# ProPrj_JS203-39-FIBER-3_2024-11-07.net
KiCad netlist of a schematic drawn in EasyEDA Pro
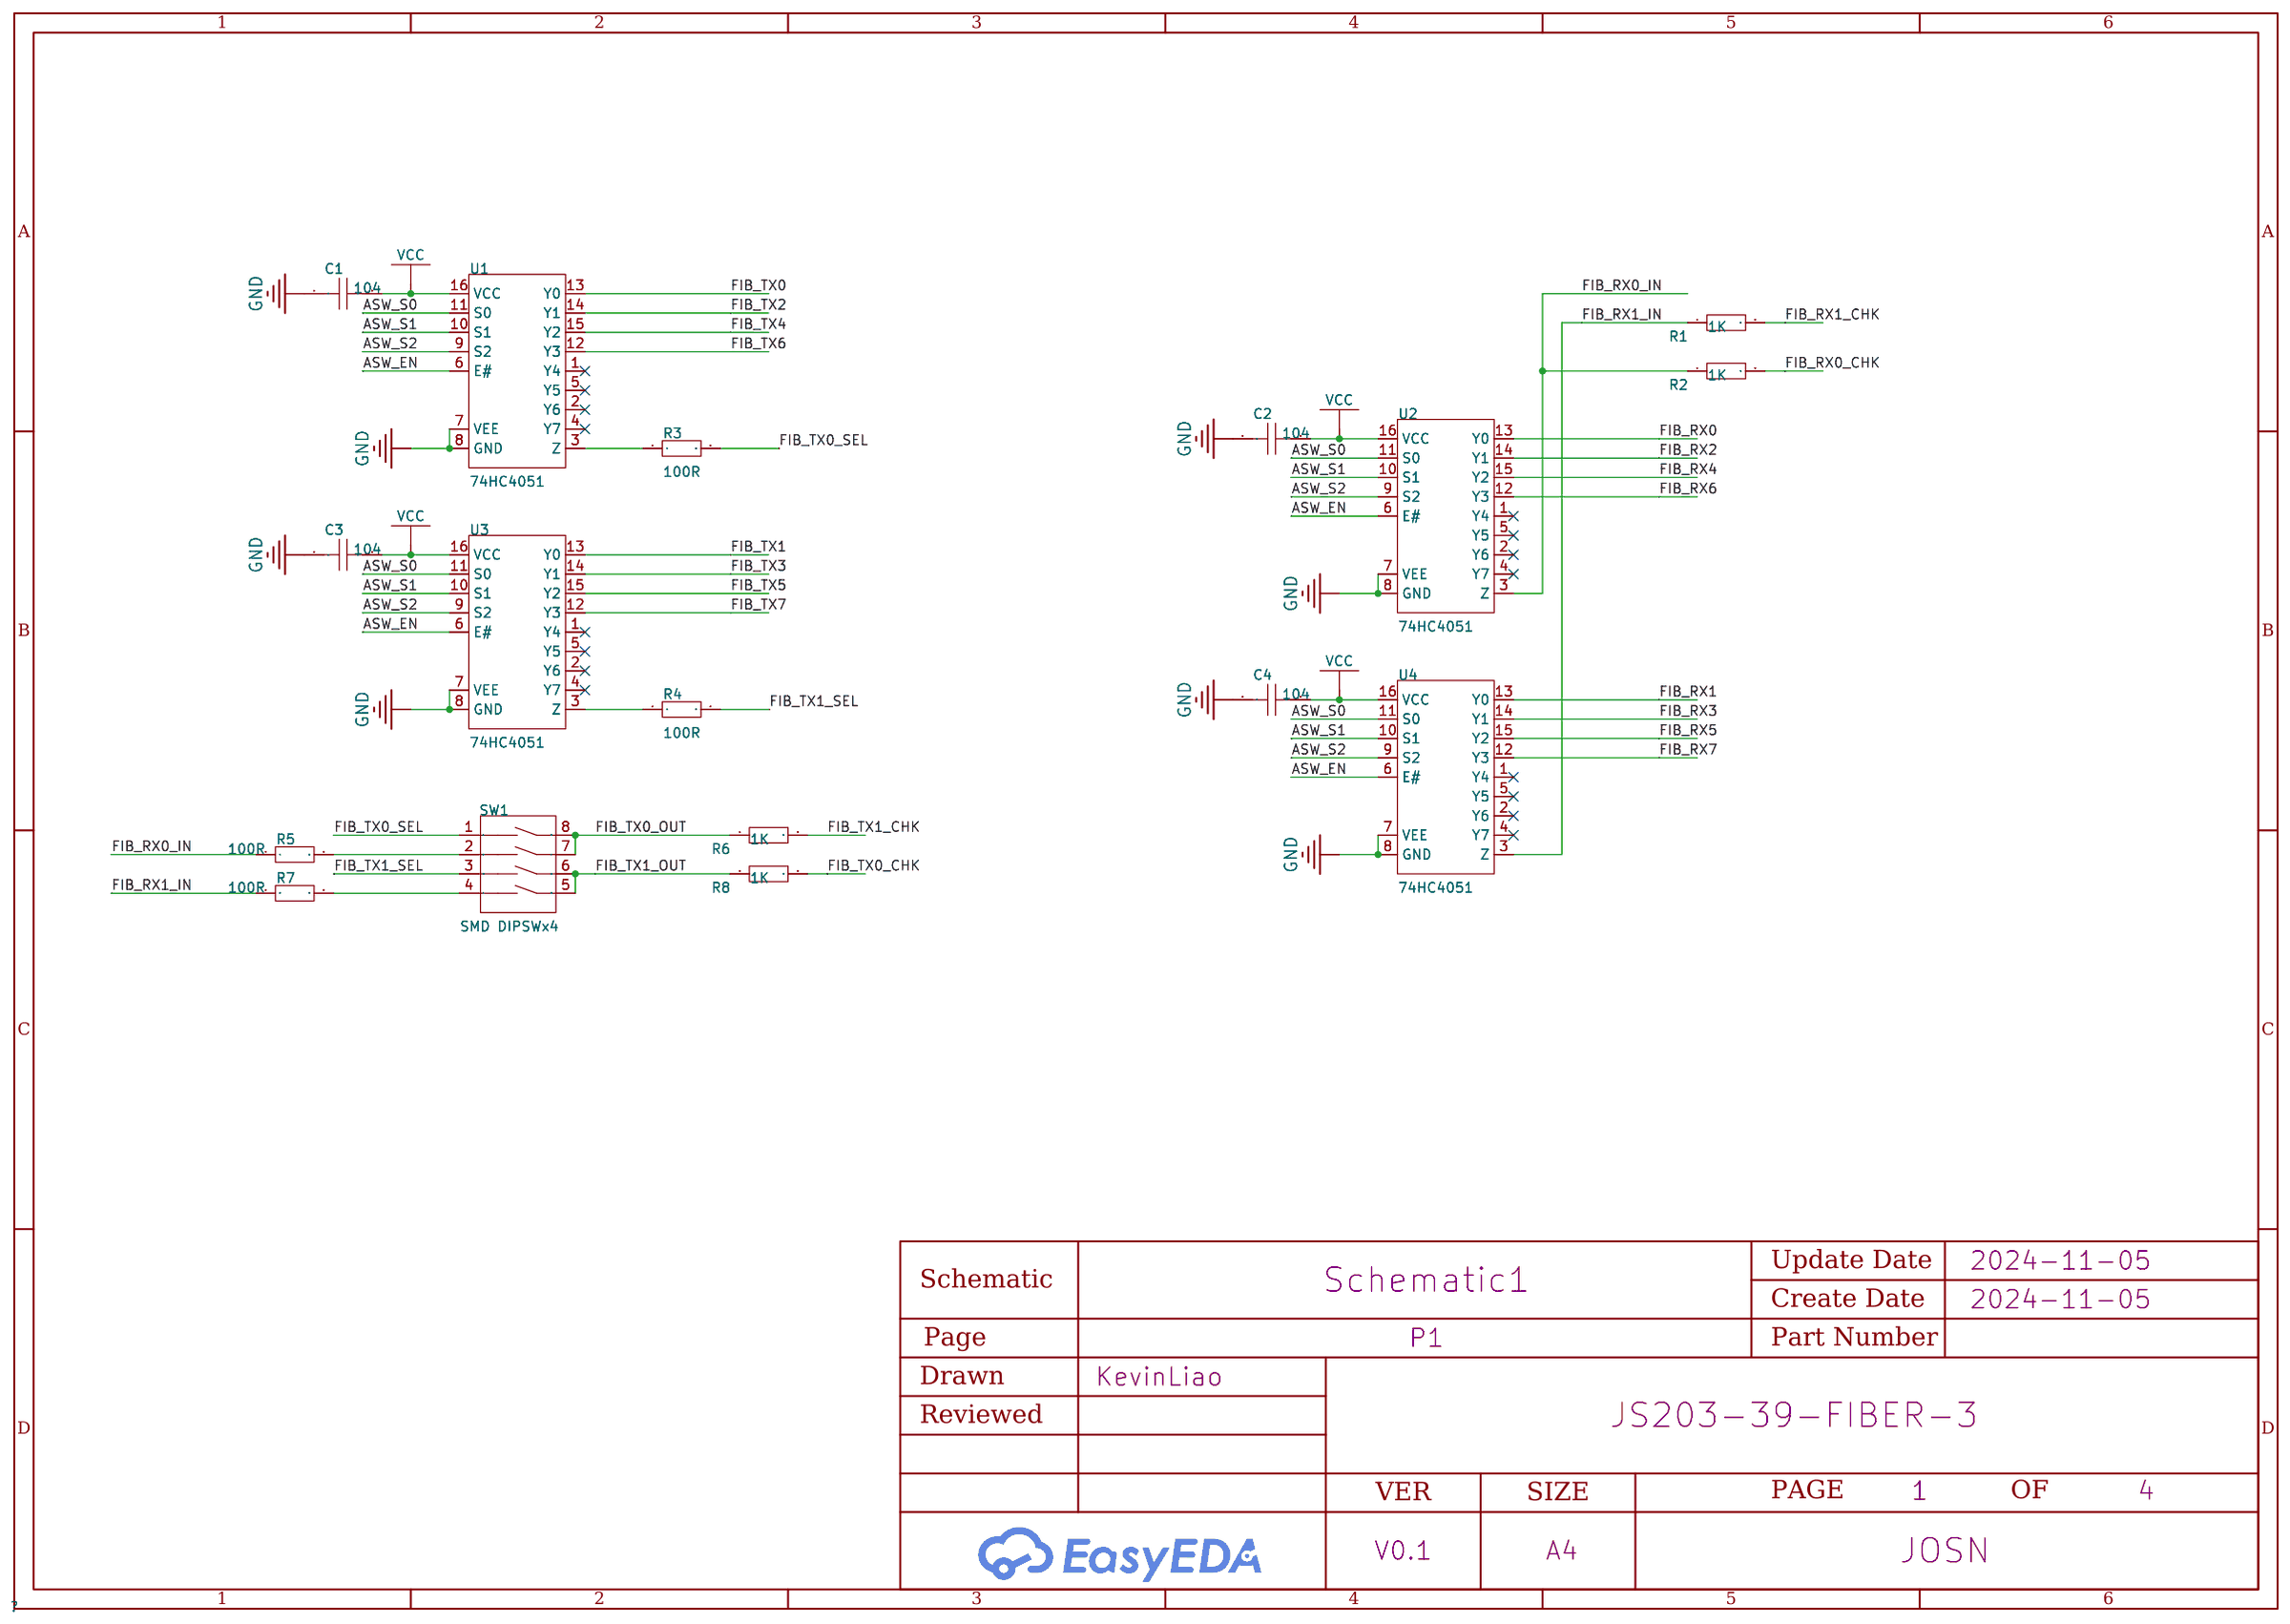
[diagram p0: P1]
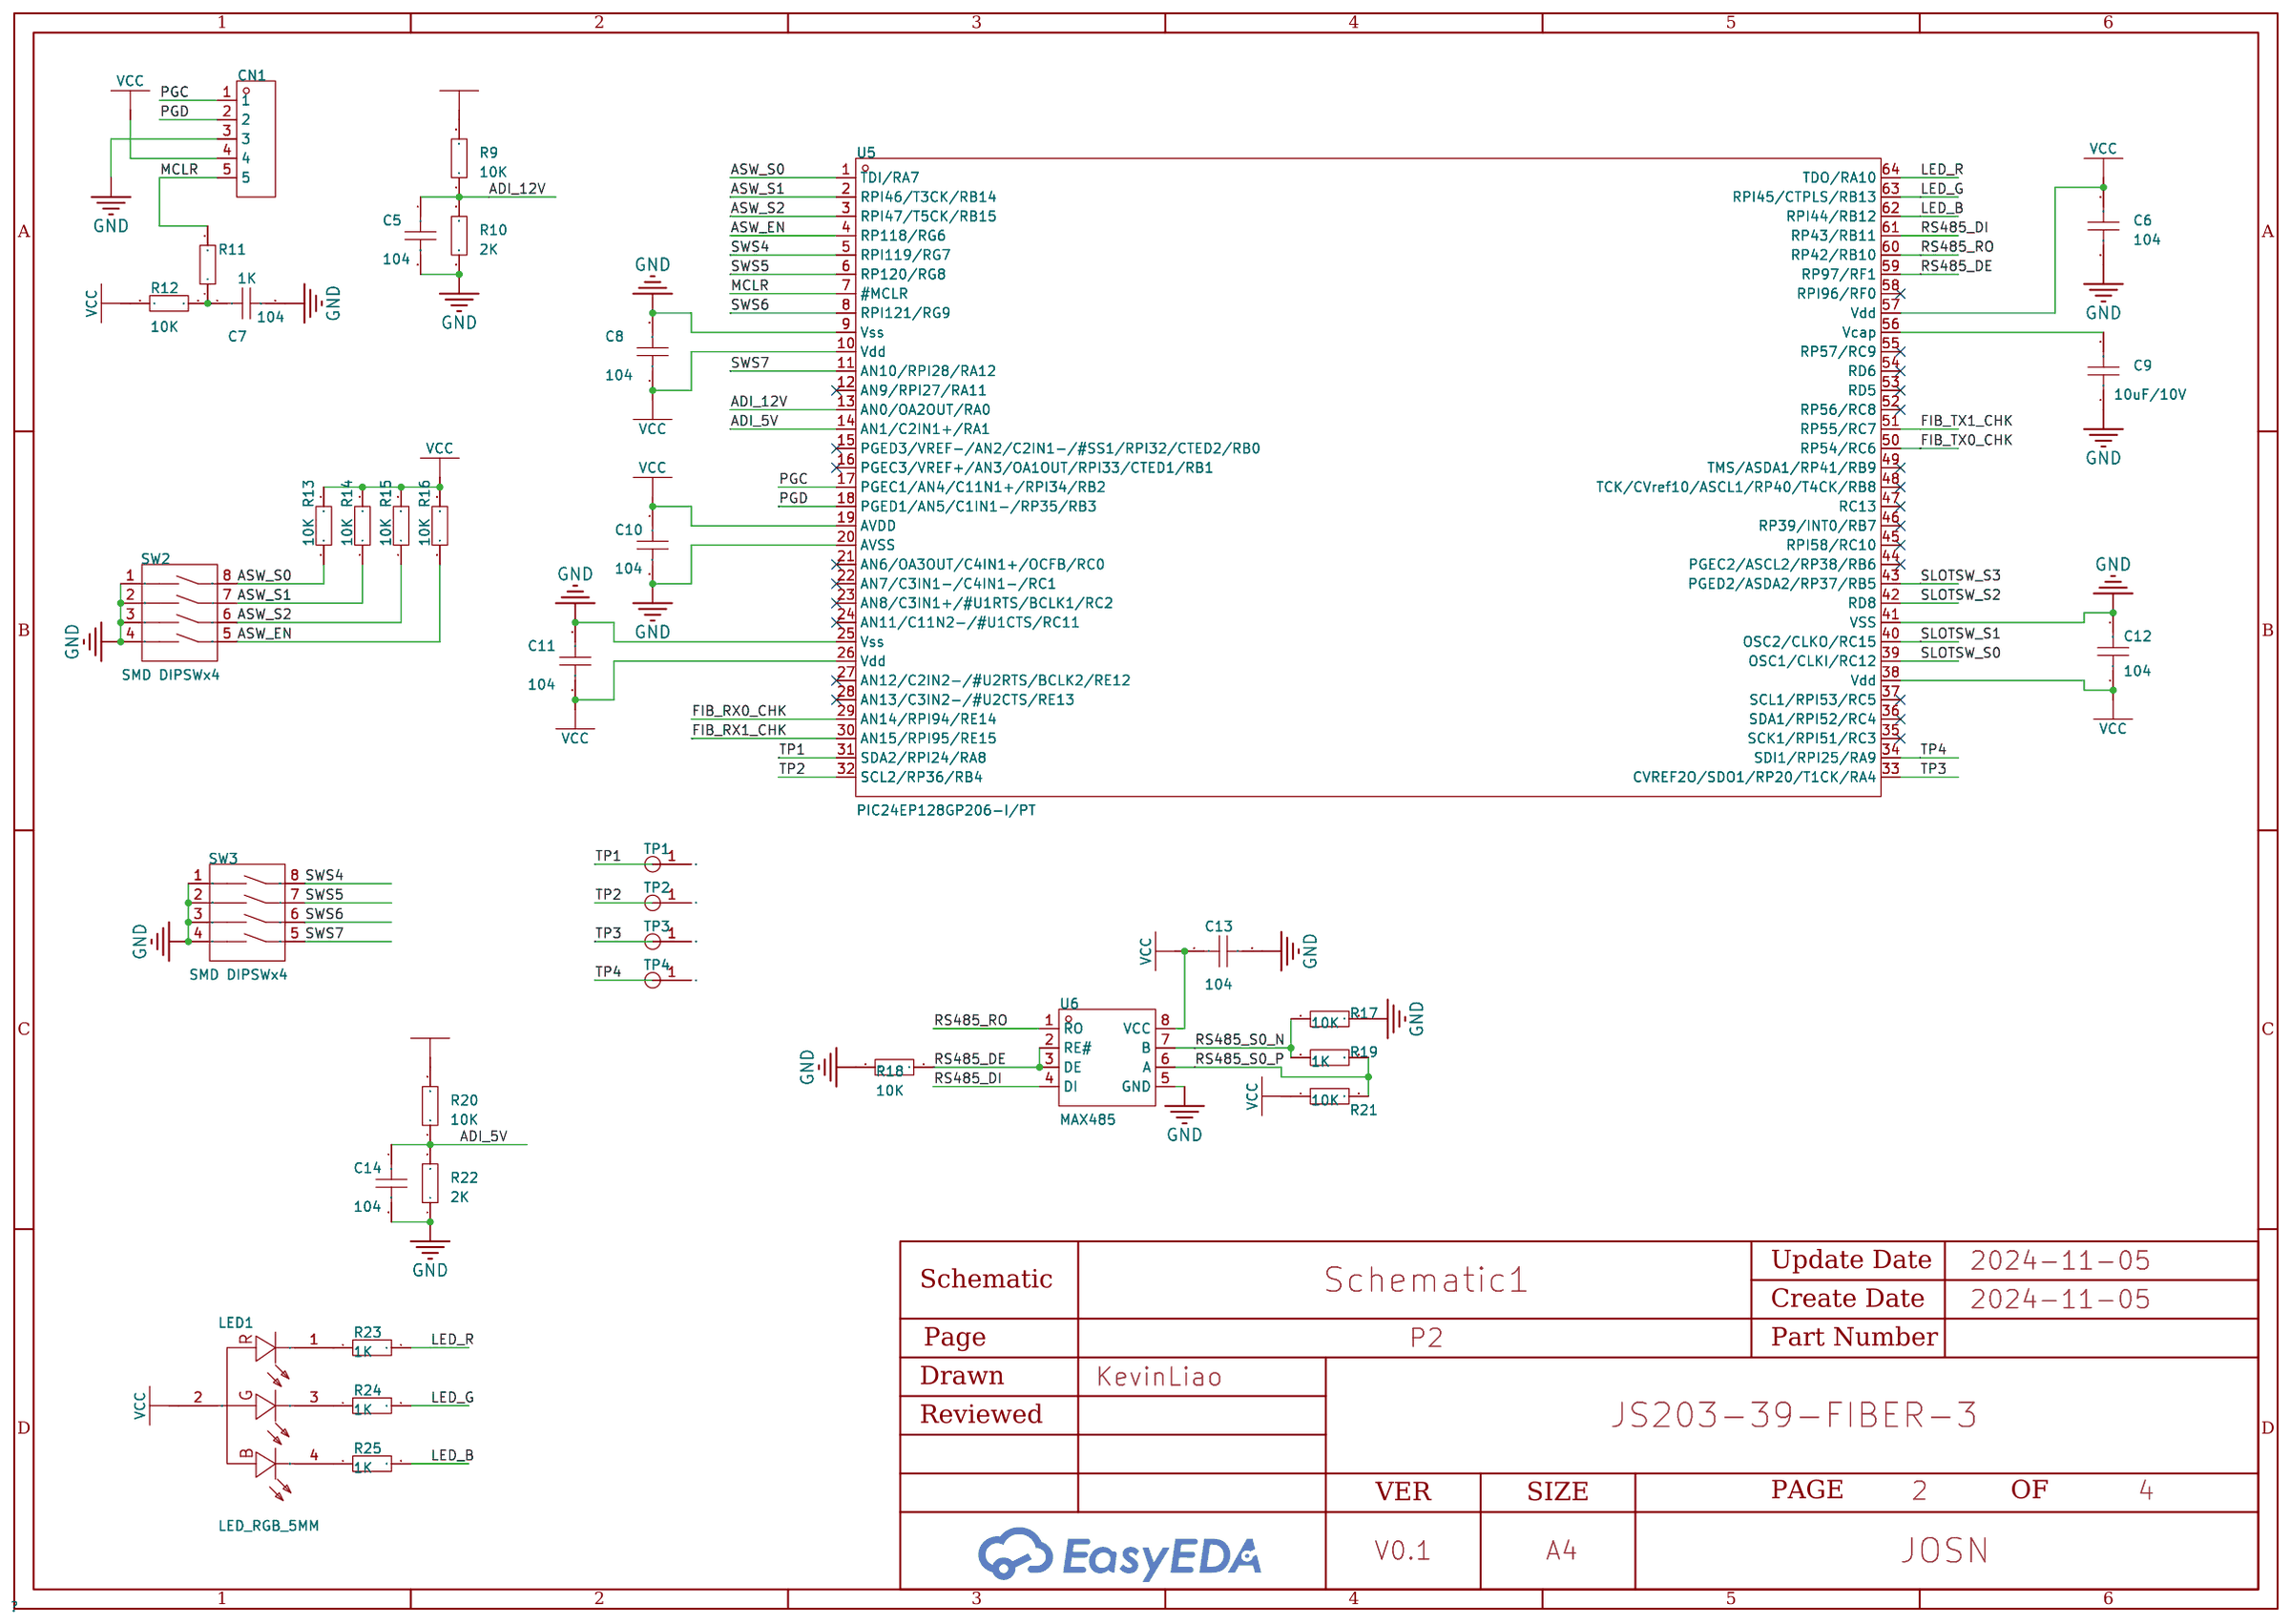
[diagram p1: P2]
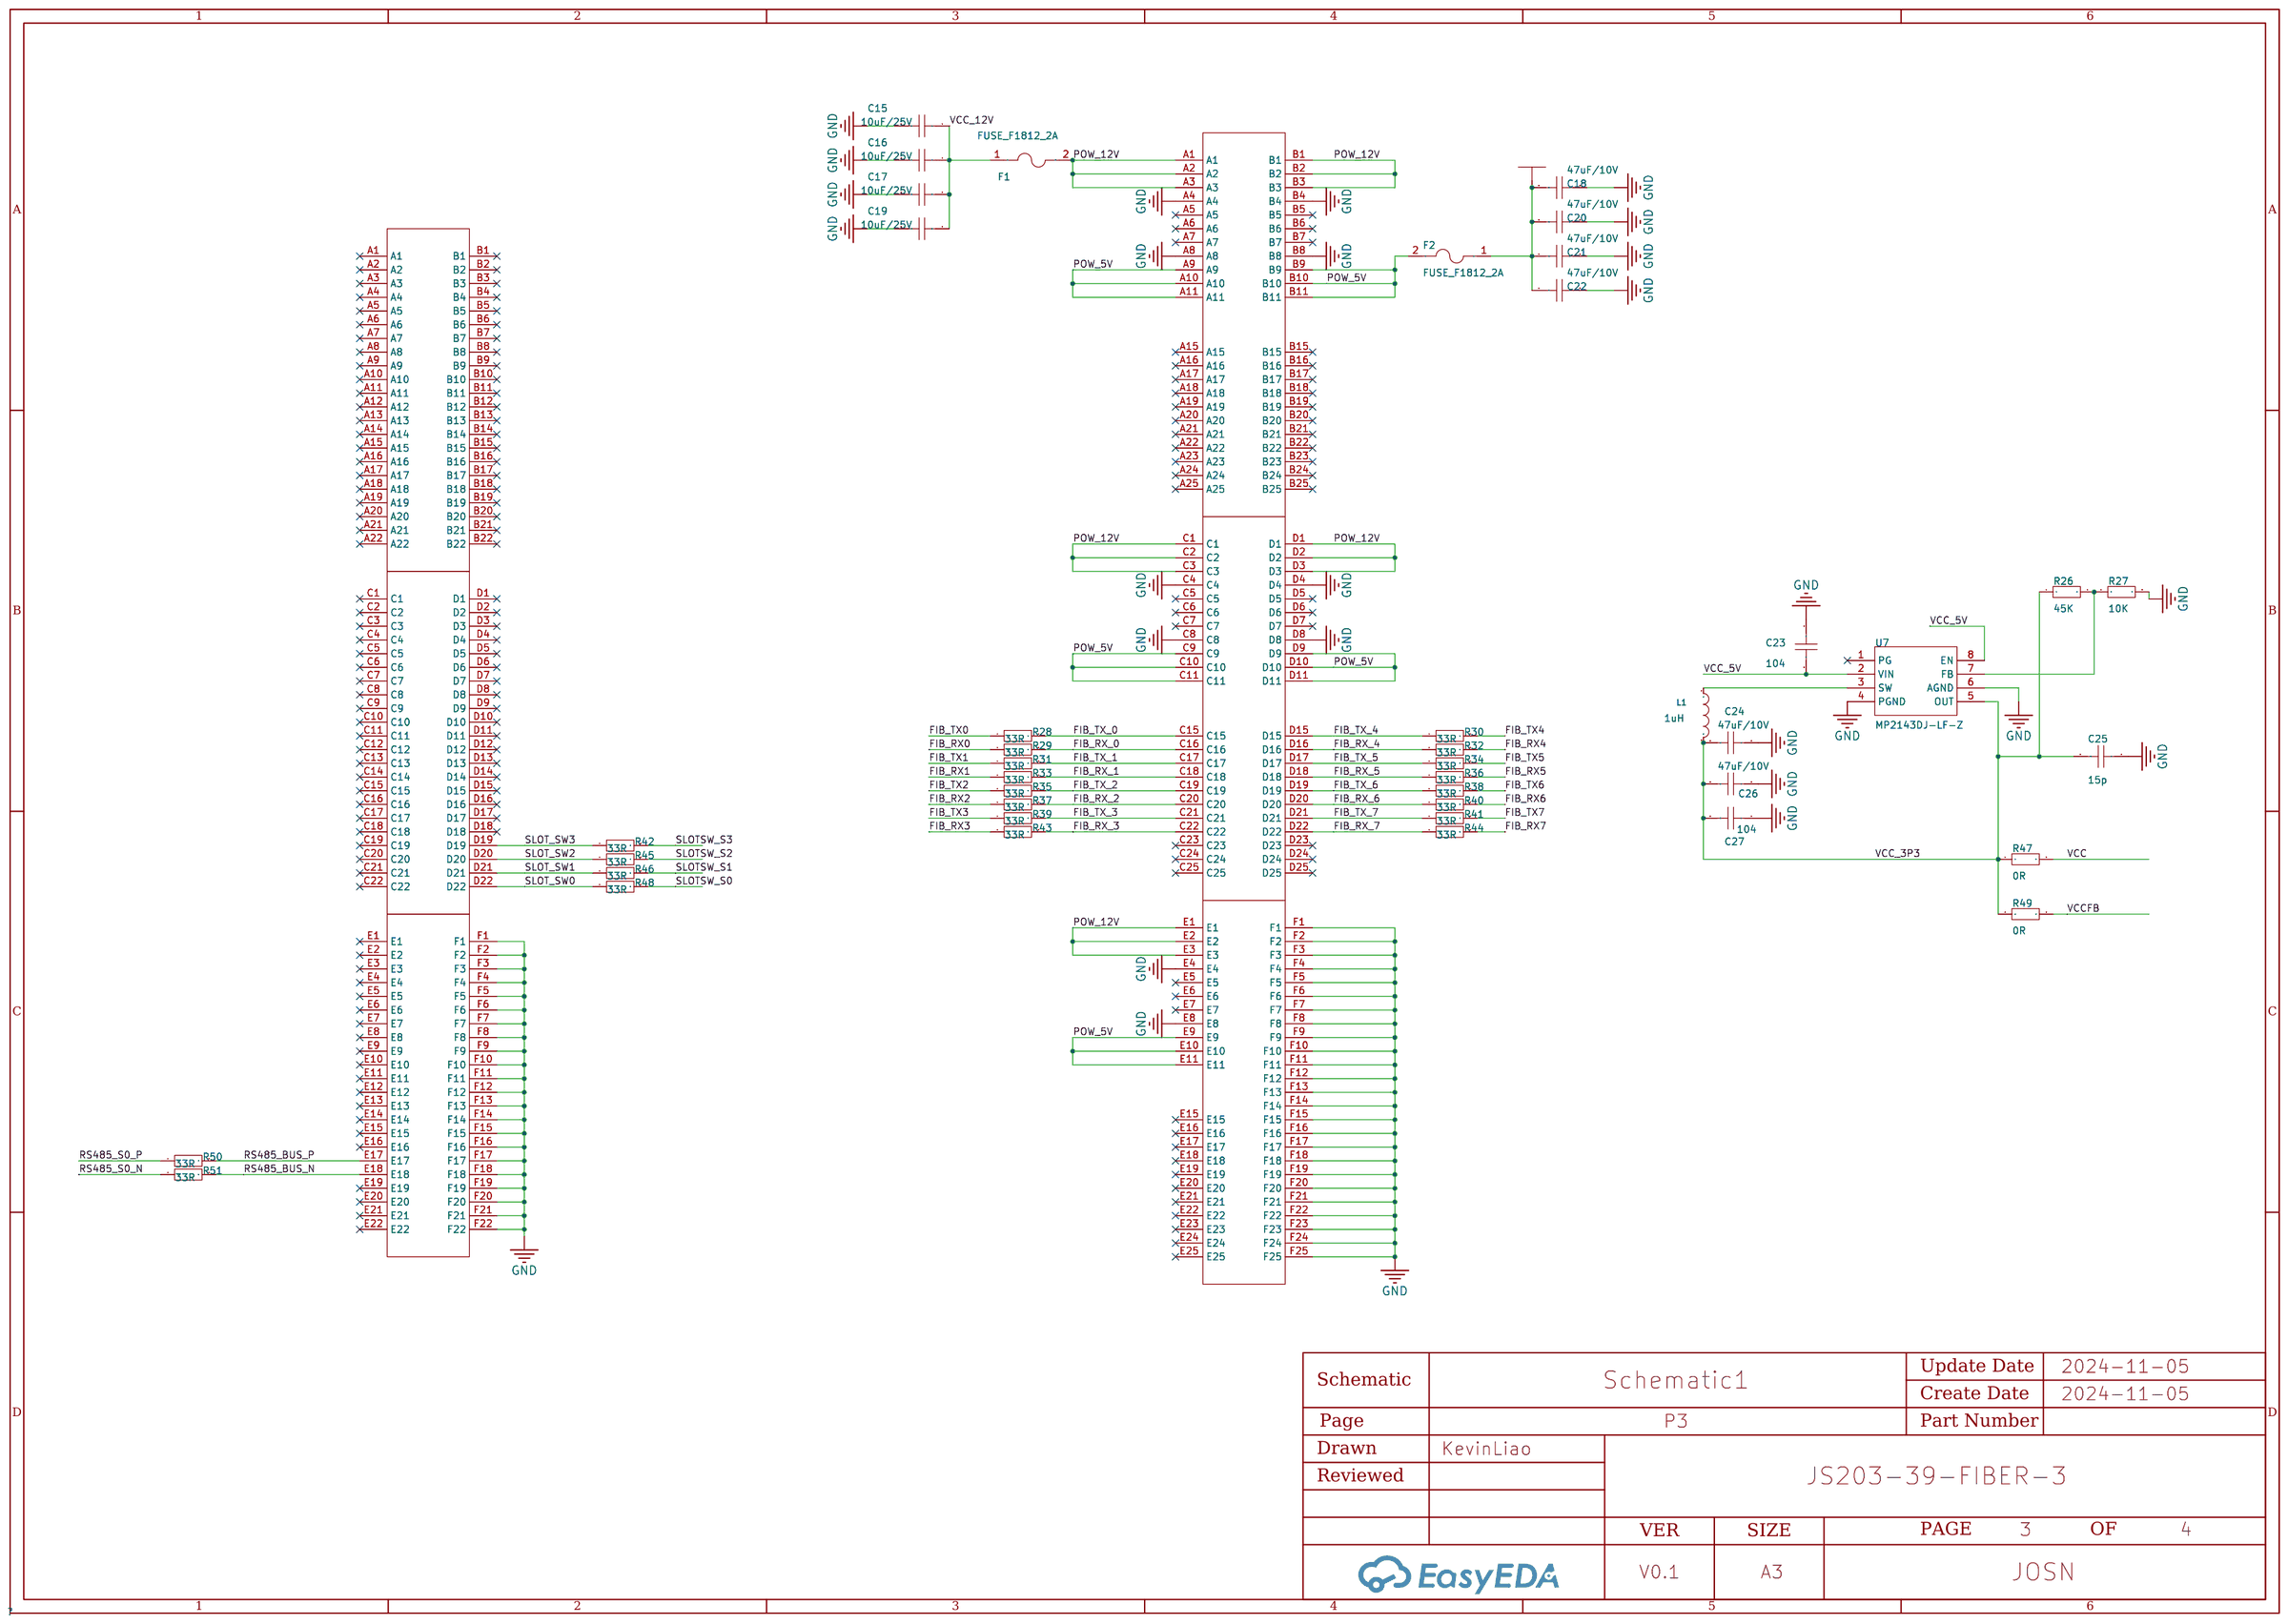
[diagram p2: P3]
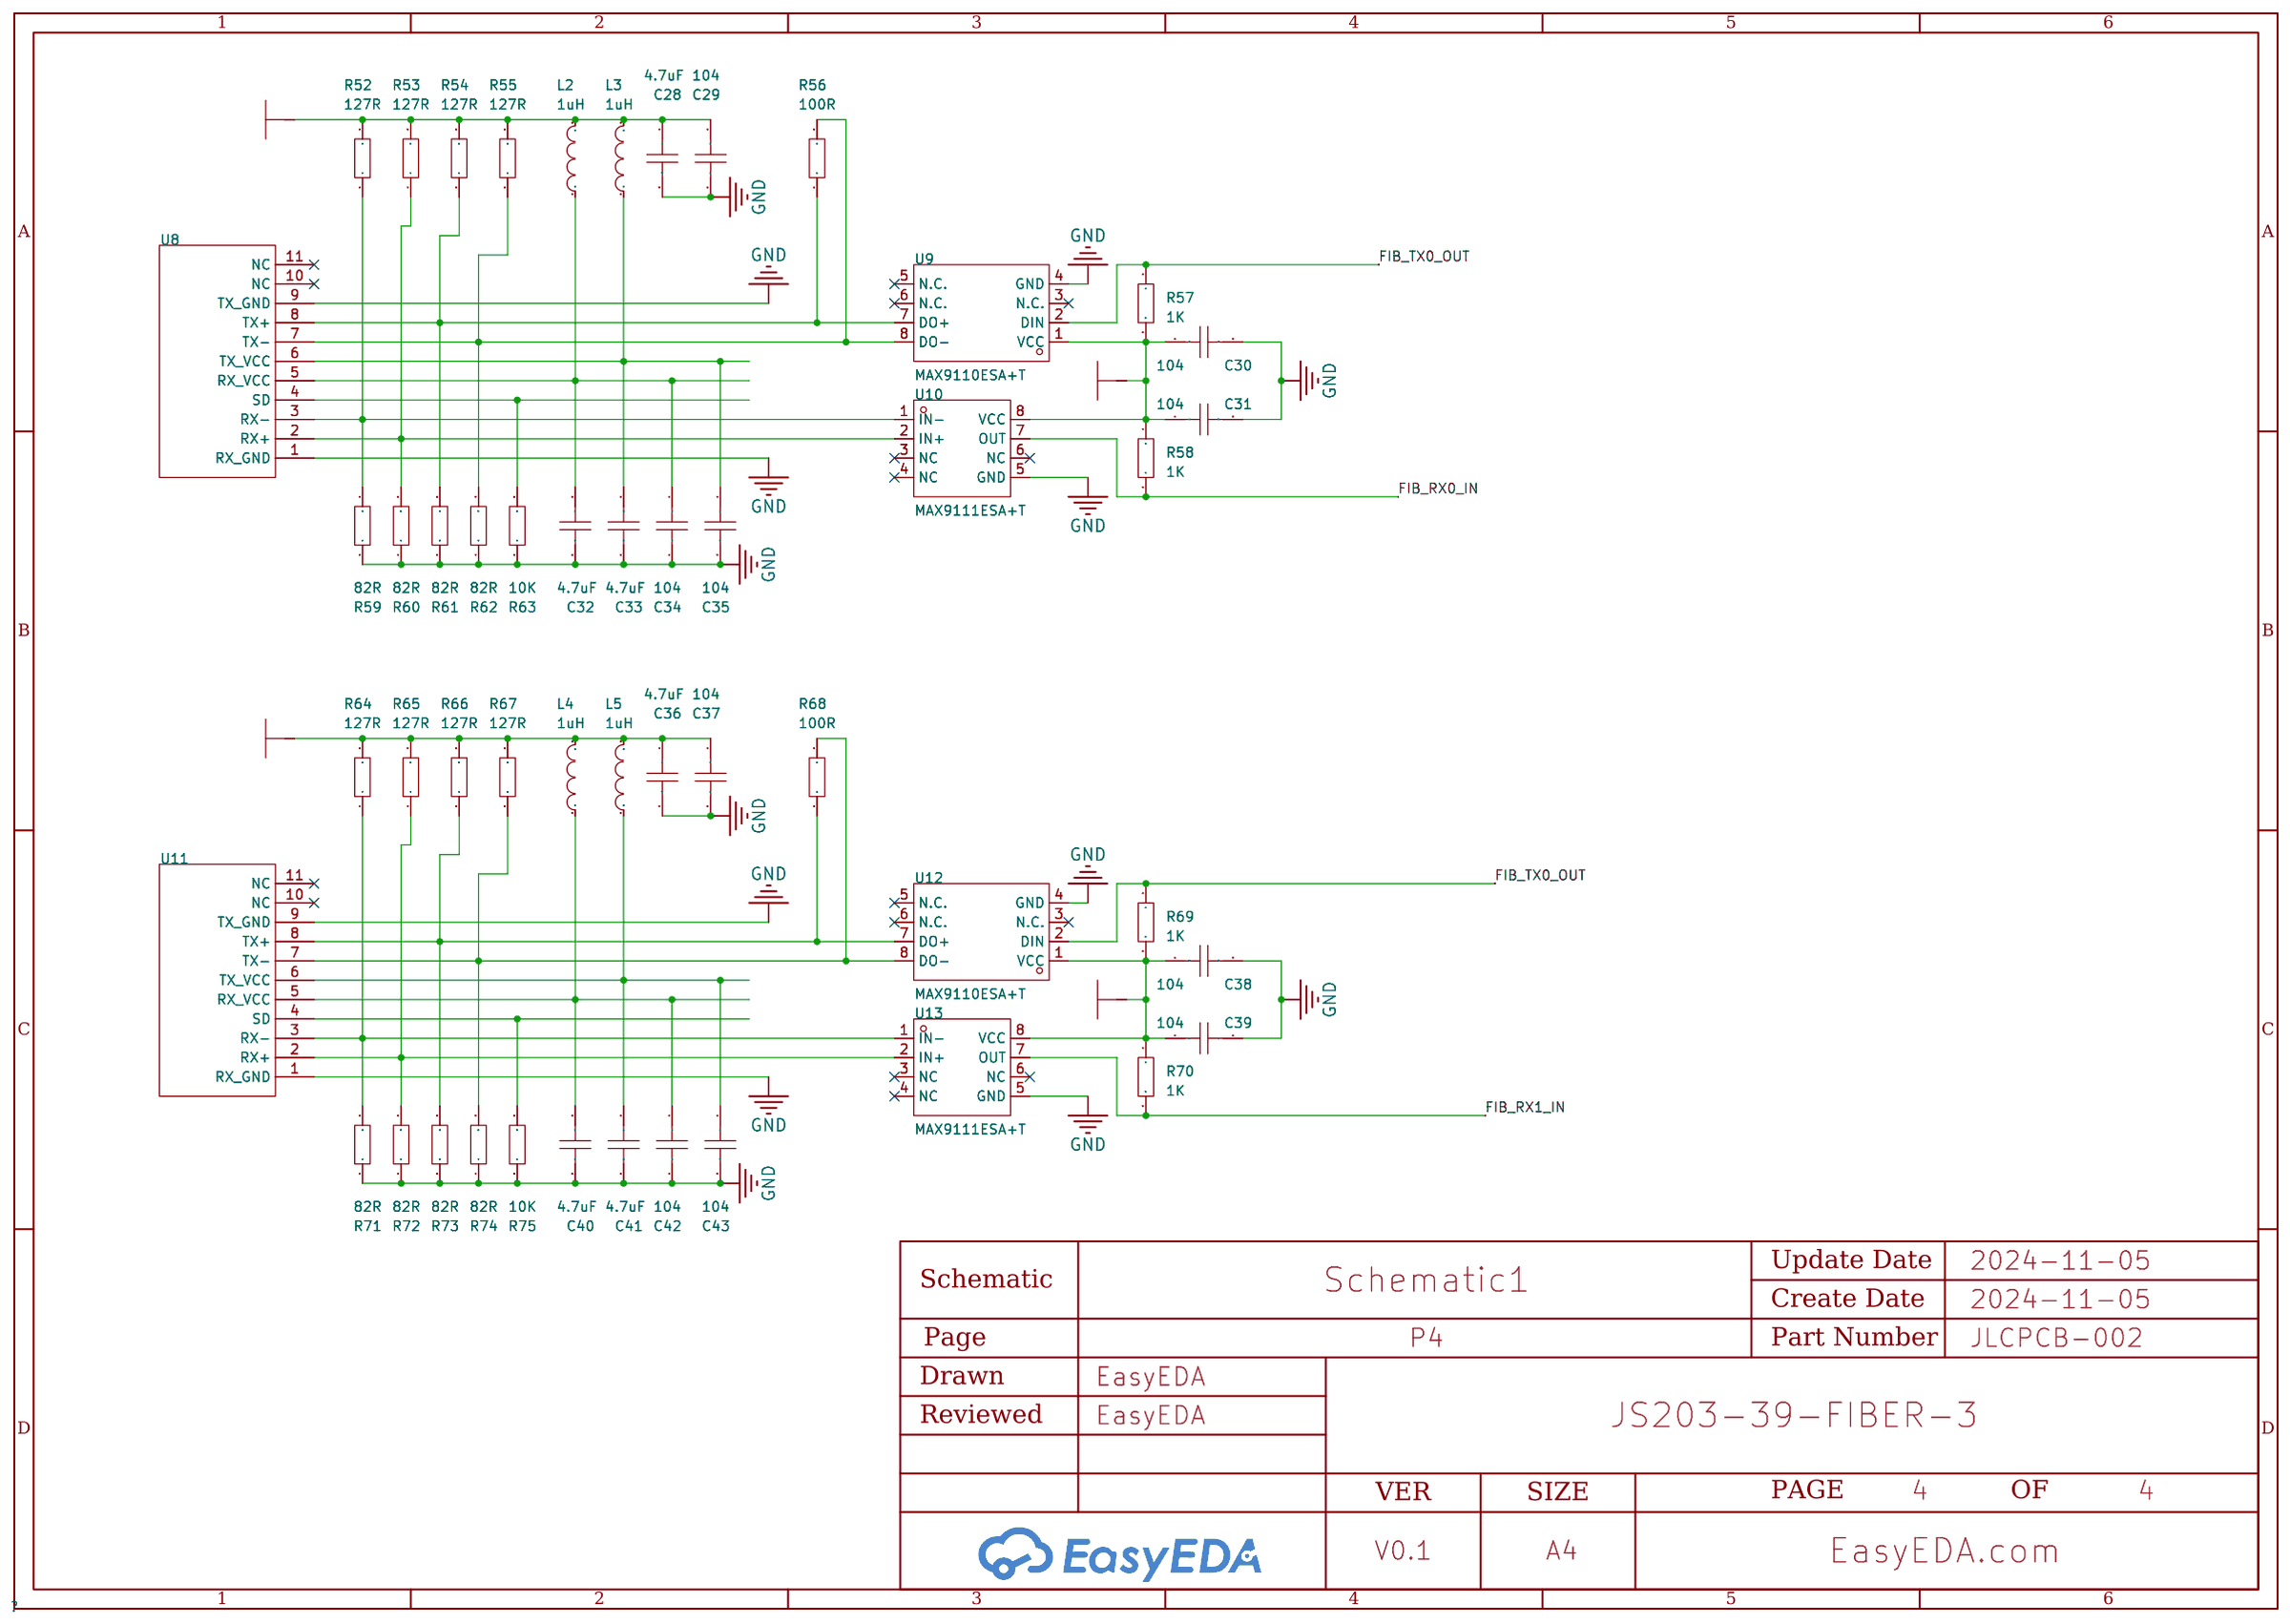
[diagram p3: P4]

(export (version "E")
  (design (tool "Eeschema 10.0.6"))
  (components
    (comp (ref "C1") (value "104") (footprint "easyedapro:C0603") (libsource (lib "easyedapro") (part "CAP")))
    (comp (ref "C2") (value "104") (footprint "easyedapro:C0603") (libsource (lib "easyedapro") (part "CAP")))
    (comp (ref "C3") (value "104") (footprint "easyedapro:C0603") (libsource (lib "easyedapro") (part "CAP")))
    (comp (ref "C4") (value "104") (footprint "easyedapro:C0603") (libsource (lib "easyedapro") (part "CAP")))
    (comp (ref "R1") (value "1K") (footprint "easyedapro:R0402") (libsource (lib "easyedapro") (part "Res")))
    (comp (ref "R2") (value "1K") (footprint "easyedapro:R0402") (libsource (lib "easyedapro") (part "Res")))
    (comp (ref "R3")
      (value "100R")
      (footprint "easyedapro:R0402")
      (libsource (lib "easyedapro") (part "Res"))
    )
    (comp (ref "R4")
      (value "100R")
      (footprint "easyedapro:R0402")
      (libsource (lib "easyedapro") (part "Res"))
    )
    (comp (ref "R5")
      (value "100R")
      (footprint "easyedapro:R0402")
      (libsource (lib "easyedapro") (part "Res"))
    )
    (comp (ref "R6") (value "1K") (footprint "easyedapro:R0402") (libsource (lib "easyedapro") (part "Res")))
    (comp (ref "R7")
      (value "100R")
      (footprint "easyedapro:R0402")
      (libsource (lib "easyedapro") (part "Res"))
    )
    (comp (ref "R8") (value "1K") (footprint "easyedapro:R0402") (libsource (lib "easyedapro") (part "Res")))
    (comp (ref "SW1")
      (value "SMD DIPSWx4")
      (footprint "easyedapro:SW-SMD_8P-L6.7-W5.4-P1.27-LS8.4")
      (libsource (lib "easyedapro") (part "DSHP04TSGER_C9900017355"))
    )
    (comp (ref "U1")
      (value "74HC4051")
      (footprint "easyedapro:TSSOP-16_L5.0-W4.4-P0.65-LS6.4-BL-1")
      (fields (field (name "Manufacturer") "onsemi(安森美)"))
      (libsource (lib "easyedapro") (part "MM74HC4051MTCX"))
    )
    (comp (ref "U2")
      (value "74HC4051")
      (footprint "easyedapro:TSSOP-16_L5.0-W4.4-P0.65-LS6.4-BL-1")
      (fields (field (name "Manufacturer") "onsemi(安森美)"))
      (libsource (lib "easyedapro") (part "MM74HC4051MTCX"))
    )
    (comp (ref "U3")
      (value "74HC4051")
      (footprint "easyedapro:TSSOP-16_L5.0-W4.4-P0.65-LS6.4-BL-1")
      (fields (field (name "Manufacturer") "onsemi(安森美)"))
      (libsource (lib "easyedapro") (part "MM74HC4051MTCX"))
    )
    (comp (ref "U4")
      (value "74HC4051")
      (footprint "easyedapro:TSSOP-16_L5.0-W4.4-P0.65-LS6.4-BL-1")
      (fields (field (name "Manufacturer") "onsemi(安森美)"))
      (libsource (lib "easyedapro") (part "MM74HC4051MTCX"))
    )
    (comp (ref "C5") (value "104") (footprint "easyedapro:C0603") (libsource (lib "easyedapro") (part "CAP")))
    (comp (ref "C6") (value "104") (footprint "easyedapro:C0603") (libsource (lib "easyedapro") (part "CAP")))
    (comp (ref "C7") (value "104") (footprint "easyedapro:C0603") (libsource (lib "easyedapro") (part "CAP")))
    (comp (ref "C8") (value "104") (footprint "easyedapro:C0603") (libsource (lib "easyedapro") (part "CAP")))
    (comp (ref "C9")
      (value "10uF/10V")
      (footprint "easyedapro:C0603")
      (libsource (lib "easyedapro") (part "CAP"))
    )
    (comp (ref "C10")
      (value "104")
      (footprint "easyedapro:C0603")
      (libsource (lib "easyedapro") (part "CAP"))
    )
    (comp (ref "C11")
      (value "104")
      (footprint "easyedapro:C0603")
      (libsource (lib "easyedapro") (part "CAP"))
    )
    (comp (ref "C12")
      (value "104")
      (footprint "easyedapro:C0603")
      (libsource (lib "easyedapro") (part "CAP"))
    )
    (comp (ref "C13")
      (value "104")
      (footprint "easyedapro:C0603")
      (libsource (lib "easyedapro") (part "CAP"))
    )
    (comp (ref "C14")
      (value "104")
      (footprint "easyedapro:C0603")
      (libsource (lib "easyedapro") (part "CAP"))
    )
    (comp (ref "CN1")
      (value "5PIN-2.0MM-90")
      (footprint "easyedapro:CONN-TH_5P-P2.00-PH5A")
      (libsource (lib "easyedapro") (part "5PIN-2.0MM-90"))
    )
    (comp (ref "LED1")
      (value "LED_RGB_5MM")
      (footprint "easyedapro:LED-TH_4P-BD5.8-P1.30")
      (libsource (lib "easyedapro") (part "三色灯2"))
    )
    (comp (ref "R9") (value "10K") (footprint "easyedapro:R0402") (libsource (lib "easyedapro") (part "Res")))
    (comp (ref "R10") (value "2K") (footprint "easyedapro:R0402") (libsource (lib "easyedapro") (part "Res")))
    (comp (ref "R11") (value "1K") (footprint "easyedapro:R0402") (libsource (lib "easyedapro") (part "Res")))
    (comp (ref "R12")
      (value "10K")
      (footprint "easyedapro:R0402")
      (libsource (lib "easyedapro") (part "Res"))
    )
    (comp (ref "R13")
      (value "10K")
      (footprint "easyedapro:R0402")
      (libsource (lib "easyedapro") (part "Res"))
    )
    (comp (ref "R14")
      (value "10K")
      (footprint "easyedapro:R0402")
      (libsource (lib "easyedapro") (part "Res"))
    )
    (comp (ref "R15")
      (value "10K")
      (footprint "easyedapro:R0402")
      (libsource (lib "easyedapro") (part "Res"))
    )
    (comp (ref "R16")
      (value "10K")
      (footprint "easyedapro:R0402")
      (libsource (lib "easyedapro") (part "Res"))
    )
    (comp (ref "R17")
      (value "10K")
      (footprint "easyedapro:R0402")
      (libsource (lib "easyedapro") (part "Res"))
    )
    (comp (ref "R18")
      (value "10K")
      (footprint "easyedapro:R0402")
      (libsource (lib "easyedapro") (part "Res"))
    )
    (comp (ref "R19") (value "1K") (footprint "easyedapro:R0402") (libsource (lib "easyedapro") (part "Res")))
    (comp (ref "R20")
      (value "10K")
      (footprint "easyedapro:R0402")
      (libsource (lib "easyedapro") (part "Res"))
    )
    (comp (ref "R21")
      (value "10K")
      (footprint "easyedapro:R0402")
      (libsource (lib "easyedapro") (part "Res"))
    )
    (comp (ref "R22") (value "2K") (footprint "easyedapro:R0402") (libsource (lib "easyedapro") (part "Res")))
    (comp (ref "R23") (value "1K") (footprint "easyedapro:R0402") (libsource (lib "easyedapro") (part "Res")))
    (comp (ref "R24") (value "1K") (footprint "easyedapro:R0402") (libsource (lib "easyedapro") (part "Res")))
    (comp (ref "R25") (value "1K") (footprint "easyedapro:R0402") (libsource (lib "easyedapro") (part "Res")))
    (comp (ref "SW2")
      (value "SMD DIPSWx4")
      (footprint "easyedapro:SW-SMD_8P-L6.7-W5.4-P1.27-LS8.4")
      (libsource (lib "easyedapro") (part "DSHP04TSGER_C9900017355"))
    )
    (comp (ref "SW3")
      (value "SMD DIPSWx4")
      (footprint "easyedapro:SW-SMD_8P-L6.7-W5.4-P1.27-LS8.4")
      (libsource (lib "easyedapro") (part "DSHP04TSGER_C9900017355"))
    )
    (comp (ref "TP1")
      (value "~")
      (footprint "easyedapro:testPoint")
      (libsource (lib "easyedapro") (part "testPoint"))
    )
    (comp (ref "TP2")
      (value "~")
      (footprint "easyedapro:testPoint")
      (libsource (lib "easyedapro") (part "testPoint"))
    )
    (comp (ref "TP3")
      (value "~")
      (footprint "easyedapro:testPoint")
      (libsource (lib "easyedapro") (part "testPoint"))
    )
    (comp (ref "TP4")
      (value "~")
      (footprint "easyedapro:testPoint")
      (libsource (lib "easyedapro") (part "testPoint"))
    )
    (comp (ref "U5")
      (value "PIC24EP128GP206-I/PT")
      (footprint "easyedapro:TQFP-64_L10.0-W10.0-P0.50-LS12.0-BL")
      (fields (field (name "Manufacturer") "MICROCHIP(美国微芯)"))
      (libsource (lib "easyedapro") (part "PIC24EP128GP206-I/PT"))
    )
    (comp (ref "U6")
      (value "MAX485")
      (footprint "easyedapro:SOIC-8_L5.0-W4.0-P1.27-LS6.0-BL")
      (fields (field (name "Manufacturer") "MSKSEMI(美森科)"))
      (libsource (lib "easyedapro") (part "MAX485ESA-MS"))
    )
    (comp (ref "C15")
      (value "10uF/25V")
      (footprint "easyedapro:C0603")
      (libsource (lib "easyedapro") (part "CAP"))
    )
    (comp (ref "C16")
      (value "10uF/25V")
      (footprint "easyedapro:C0603")
      (libsource (lib "easyedapro") (part "CAP"))
    )
    (comp (ref "C17")
      (value "10uF/25V")
      (footprint "easyedapro:C0603")
      (libsource (lib "easyedapro") (part "CAP"))
    )
    (comp (ref "C18")
      (value "47uF/10V")
      (footprint "easyedapro:C0603")
      (libsource (lib "easyedapro") (part "CAP"))
    )
    (comp (ref "C19")
      (value "10uF/25V")
      (footprint "easyedapro:C0603")
      (libsource (lib "easyedapro") (part "CAP"))
    )
    (comp (ref "C20")
      (value "47uF/10V")
      (footprint "easyedapro:C0603")
      (libsource (lib "easyedapro") (part "CAP"))
    )
    (comp (ref "C21")
      (value "47uF/10V")
      (footprint "easyedapro:C0603")
      (libsource (lib "easyedapro") (part "CAP"))
    )
    (comp (ref "C22")
      (value "47uF/10V")
      (footprint "easyedapro:C0603")
      (libsource (lib "easyedapro") (part "CAP"))
    )
    (comp (ref "C23")
      (value "104")
      (footprint "easyedapro:C0603")
      (libsource (lib "easyedapro") (part "CAP"))
    )
    (comp (ref "C24")
      (value "47uF/10V")
      (footprint "easyedapro:C0603")
      (libsource (lib "easyedapro") (part "CAP"))
    )
    (comp (ref "C25")
      (value "15p")
      (footprint "easyedapro:C0603")
      (libsource (lib "easyedapro") (part "CAP"))
    )
    (comp (ref "C26")
      (value "47uF/10V")
      (footprint "easyedapro:C0603")
      (libsource (lib "easyedapro") (part "CAP"))
    )
    (comp (ref "C27")
      (value "104")
      (footprint "easyedapro:C0603")
      (libsource (lib "easyedapro") (part "CAP"))
    )
    (comp (ref "CON1") (value "CPCI-CON-B") (libsource (lib "easyedapro") (part "pci-con-b")))
    (comp (ref "CON2") (value "CPCI-CON-A") (libsource (lib "easyedapro") (part "cpci-con-a")))
    (comp (ref "F1")
      (value "FUSE_F1812_2A")
      (footprint "easyedapro:F1812")
      (libsource (lib "easyedapro") (part "FUSE_F1812_FUSE"))
    )
    (comp (ref "F2")
      (value "FUSE_F1812_2A")
      (footprint "easyedapro:F1812")
      (libsource (lib "easyedapro") (part "FUSE_F1812_FUSE"))
    )
    (comp (ref "L1")
      (value "1uH")
      (footprint "easyedapro:IND-SMD_L4.0-W4.0-A")
      (fields
        (field (name "Manufacturer Part") "XFL4020-152MEC")
        (field (name "Manufacturer") "Coilcraft(线艺)")
      )
      (libsource (lib "easyedapro") (part "XFL4020-152MEC"))
    )
    (comp (ref "R26")
      (value "45K")
      (footprint "easyedapro:R0402")
      (libsource (lib "easyedapro") (part "Res"))
    )
    (comp (ref "R27")
      (value "10K")
      (footprint "easyedapro:R0402")
      (libsource (lib "easyedapro") (part "Res"))
    )
    (comp (ref "R28")
      (value "33R")
      (footprint "easyedapro:R0402")
      (libsource (lib "easyedapro") (part "Res"))
    )
    (comp (ref "R29")
      (value "33R")
      (footprint "easyedapro:R0402")
      (libsource (lib "easyedapro") (part "Res"))
    )
    (comp (ref "R30")
      (value "33R")
      (footprint "easyedapro:R0402")
      (libsource (lib "easyedapro") (part "Res"))
    )
    (comp (ref "R31")
      (value "33R")
      (footprint "easyedapro:R0402")
      (libsource (lib "easyedapro") (part "Res"))
    )
    (comp (ref "R32")
      (value "33R")
      (footprint "easyedapro:R0402")
      (libsource (lib "easyedapro") (part "Res"))
    )
    (comp (ref "R33")
      (value "33R")
      (footprint "easyedapro:R0402")
      (libsource (lib "easyedapro") (part "Res"))
    )
    (comp (ref "R34")
      (value "33R")
      (footprint "easyedapro:R0402")
      (libsource (lib "easyedapro") (part "Res"))
    )
    (comp (ref "R35")
      (value "33R")
      (footprint "easyedapro:R0402")
      (libsource (lib "easyedapro") (part "Res"))
    )
    (comp (ref "R36")
      (value "33R")
      (footprint "easyedapro:R0402")
      (libsource (lib "easyedapro") (part "Res"))
    )
    (comp (ref "R37")
      (value "33R")
      (footprint "easyedapro:R0402")
      (libsource (lib "easyedapro") (part "Res"))
    )
    (comp (ref "R38")
      (value "33R")
      (footprint "easyedapro:R0402")
      (libsource (lib "easyedapro") (part "Res"))
    )
    (comp (ref "R39")
      (value "33R")
      (footprint "easyedapro:R0402")
      (libsource (lib "easyedapro") (part "Res"))
    )
    (comp (ref "R40")
      (value "33R")
      (footprint "easyedapro:R0402")
      (libsource (lib "easyedapro") (part "Res"))
    )
    (comp (ref "R41")
      (value "33R")
      (footprint "easyedapro:R0402")
      (libsource (lib "easyedapro") (part "Res"))
    )
    (comp (ref "R42")
      (value "33R")
      (footprint "easyedapro:R0402")
      (libsource (lib "easyedapro") (part "Res"))
    )
    (comp (ref "R43")
      (value "33R")
      (footprint "easyedapro:R0402")
      (libsource (lib "easyedapro") (part "Res"))
    )
    (comp (ref "R44")
      (value "33R")
      (footprint "easyedapro:R0402")
      (libsource (lib "easyedapro") (part "Res"))
    )
    (comp (ref "R45")
      (value "33R")
      (footprint "easyedapro:R0402")
      (libsource (lib "easyedapro") (part "Res"))
    )
    (comp (ref "R46")
      (value "33R")
      (footprint "easyedapro:R0402")
      (libsource (lib "easyedapro") (part "Res"))
    )
    (comp (ref "R47") (value "0R") (footprint "easyedapro:R0402") (libsource (lib "easyedapro") (part "Res")))
    (comp (ref "R48")
      (value "33R")
      (footprint "easyedapro:R0402")
      (libsource (lib "easyedapro") (part "Res"))
    )
    (comp (ref "R49") (value "0R") (footprint "easyedapro:R0402") (libsource (lib "easyedapro") (part "Res")))
    (comp (ref "R50")
      (value "33R")
      (footprint "easyedapro:R0402")
      (libsource (lib "easyedapro") (part "Res"))
    )
    (comp (ref "R51")
      (value "33R")
      (footprint "easyedapro:R0402")
      (libsource (lib "easyedapro") (part "Res"))
    )
    (comp (ref "U7")
      (value "MP2143DJ-LF-Z")
      (footprint "easyedapro:TSOT-23-8_L2.9-W1.6-P0.65-LS2.8-BR")
      (libsource (lib "easyedapro") (part "MP2143DJ-LF-Z"))
    )
    (comp (ref "C28")
      (value "4.7uF")
      (footprint "easyedapro:C0603")
      (libsource (lib "easyedapro") (part "CAP"))
    )
    (comp (ref "C29")
      (value "104")
      (footprint "easyedapro:C0603")
      (libsource (lib "easyedapro") (part "CAP"))
    )
    (comp (ref "C30")
      (value "104")
      (footprint "easyedapro:C0603")
      (libsource (lib "easyedapro") (part "CAP"))
    )
    (comp (ref "C31")
      (value "104")
      (footprint "easyedapro:C0603")
      (libsource (lib "easyedapro") (part "CAP"))
    )
    (comp (ref "C32")
      (value "4.7uF")
      (footprint "easyedapro:C0603")
      (libsource (lib "easyedapro") (part "CAP"))
    )
    (comp (ref "C33")
      (value "4.7uF")
      (footprint "easyedapro:C0603")
      (libsource (lib "easyedapro") (part "CAP"))
    )
    (comp (ref "C34")
      (value "104")
      (footprint "easyedapro:C0603")
      (libsource (lib "easyedapro") (part "CAP"))
    )
    (comp (ref "C35")
      (value "104")
      (footprint "easyedapro:C0603")
      (libsource (lib "easyedapro") (part "CAP"))
    )
    (comp (ref "C36")
      (value "4.7uF")
      (footprint "easyedapro:C0603")
      (libsource (lib "easyedapro") (part "CAP"))
    )
    (comp (ref "C37")
      (value "104")
      (footprint "easyedapro:C0603")
      (libsource (lib "easyedapro") (part "CAP"))
    )
    (comp (ref "C38")
      (value "104")
      (footprint "easyedapro:C0603")
      (libsource (lib "easyedapro") (part "CAP"))
    )
    (comp (ref "C39")
      (value "104")
      (footprint "easyedapro:C0603")
      (libsource (lib "easyedapro") (part "CAP"))
    )
    (comp (ref "C40")
      (value "4.7uF")
      (footprint "easyedapro:C0603")
      (libsource (lib "easyedapro") (part "CAP"))
    )
    (comp (ref "C41")
      (value "4.7uF")
      (footprint "easyedapro:C0603")
      (libsource (lib "easyedapro") (part "CAP"))
    )
    (comp (ref "C42")
      (value "104")
      (footprint "easyedapro:C0603")
      (libsource (lib "easyedapro") (part "CAP"))
    )
    (comp (ref "C43")
      (value "104")
      (footprint "easyedapro:C0603")
      (libsource (lib "easyedapro") (part "CAP"))
    )
    (comp (ref "L2") (value "1uH") (footprint "easyedapro:L0805") (libsource (lib "easyedapro") (part "电感")))
    (comp (ref "L3") (value "1uH") (footprint "easyedapro:L0805") (libsource (lib "easyedapro") (part "电感")))
    (comp (ref "L4") (value "1uH") (footprint "easyedapro:L0805") (libsource (lib "easyedapro") (part "电感")))
    (comp (ref "L5") (value "1uH") (footprint "easyedapro:L0805") (libsource (lib "easyedapro") (part "电感")))
    (comp (ref "R52")
      (value "127R")
      (footprint "easyedapro:R0402")
      (libsource (lib "easyedapro") (part "Res"))
    )
    (comp (ref "R53")
      (value "127R")
      (footprint "easyedapro:R0402")
      (libsource (lib "easyedapro") (part "Res"))
    )
    (comp (ref "R54")
      (value "127R")
      (footprint "easyedapro:R0402")
      (libsource (lib "easyedapro") (part "Res"))
    )
    (comp (ref "R55")
      (value "127R")
      (footprint "easyedapro:R0402")
      (libsource (lib "easyedapro") (part "Res"))
    )
    (comp (ref "R56")
      (value "100R")
      (footprint "easyedapro:R0402")
      (libsource (lib "easyedapro") (part "Res"))
    )
    (comp (ref "R57") (value "1K") (footprint "easyedapro:R0402") (libsource (lib "easyedapro") (part "Res")))
    (comp (ref "R58") (value "1K") (footprint "easyedapro:R0402") (libsource (lib "easyedapro") (part "Res")))
    (comp (ref "R59")
      (value "82R")
      (footprint "easyedapro:R0402")
      (libsource (lib "easyedapro") (part "Res"))
    )
    (comp (ref "R60")
      (value "82R")
      (footprint "easyedapro:R0402")
      (libsource (lib "easyedapro") (part "Res"))
    )
    (comp (ref "R61")
      (value "82R")
      (footprint "easyedapro:R0402")
      (libsource (lib "easyedapro") (part "Res"))
    )
    (comp (ref "R62")
      (value "82R")
      (footprint "easyedapro:R0402")
      (libsource (lib "easyedapro") (part "Res"))
    )
    (comp (ref "R63")
      (value "10K")
      (footprint "easyedapro:R0402")
      (libsource (lib "easyedapro") (part "Res"))
    )
    (comp (ref "R64")
      (value "127R")
      (footprint "easyedapro:R0402")
      (libsource (lib "easyedapro") (part "Res"))
    )
    (comp (ref "R65")
      (value "127R")
      (footprint "easyedapro:R0402")
      (libsource (lib "easyedapro") (part "Res"))
    )
    (comp (ref "R66")
      (value "127R")
      (footprint "easyedapro:R0402")
      (libsource (lib "easyedapro") (part "Res"))
    )
    (comp (ref "R67")
      (value "127R")
      (footprint "easyedapro:R0402")
      (libsource (lib "easyedapro") (part "Res"))
    )
    (comp (ref "R68")
      (value "100R")
      (footprint "easyedapro:R0402")
      (libsource (lib "easyedapro") (part "Res"))
    )
    (comp (ref "R69") (value "1K") (footprint "easyedapro:R0402") (libsource (lib "easyedapro") (part "Res")))
    (comp (ref "R70") (value "1K") (footprint "easyedapro:R0402") (libsource (lib "easyedapro") (part "Res")))
    (comp (ref "R71")
      (value "82R")
      (footprint "easyedapro:R0402")
      (libsource (lib "easyedapro") (part "Res"))
    )
    (comp (ref "R72")
      (value "82R")
      (footprint "easyedapro:R0402")
      (libsource (lib "easyedapro") (part "Res"))
    )
    (comp (ref "R73")
      (value "82R")
      (footprint "easyedapro:R0402")
      (libsource (lib "easyedapro") (part "Res"))
    )
    (comp (ref "R74")
      (value "82R")
      (footprint "easyedapro:R0402")
      (libsource (lib "easyedapro") (part "Res"))
    )
    (comp (ref "R75")
      (value "10K")
      (footprint "easyedapro:R0402")
      (libsource (lib "easyedapro") (part "Res"))
    )
    (comp (ref "U8")
      (value "~")
      (footprint "easyedapro:AFBR-5803TZ")
      (libsource (lib "easyedapro") (part "AFBR-5803TZ"))
    )
    (comp (ref "U9")
      (value "MAX9110ESA+T")
      (footprint "easyedapro:SOIC-8_L4.9-W3.9-P1.27-LS6.0-BL")
      (fields (field (name "Manufacturer") "ADI(亚德诺)/MAXIM(美信)"))
      (libsource (lib "easyedapro") (part "MAX9110ESA+T"))
    )
    (comp (ref "U10")
      (value "MAX9111ESA+T")
      (footprint "easyedapro:SOIC-8_L4.9-W3.9-P1.27-LS6.0-BL")
      (fields (field (name "Manufacturer") "ADI(亚德诺)/MAXIM(美信)"))
      (libsource (lib "easyedapro") (part "MAX9111ESA+T"))
    )
    (comp (ref "U11")
      (value "~")
      (footprint "easyedapro:AFBR-5803TZ")
      (libsource (lib "easyedapro") (part "AFBR-5803TZ"))
    )
    (comp (ref "U12")
      (value "MAX9110ESA+T")
      (footprint "easyedapro:SOIC-8_L4.9-W3.9-P1.27-LS6.0-BL")
      (fields (field (name "Manufacturer") "ADI(亚德诺)/MAXIM(美信)"))
      (libsource (lib "easyedapro") (part "MAX9110ESA+T"))
    )
    (comp (ref "U13")
      (value "MAX9111ESA+T")
      (footprint "easyedapro:SOIC-8_L4.9-W3.9-P1.27-LS6.0-BL")
      (fields (field (name "Manufacturer") "ADI(亚德诺)/MAXIM(美信)"))
      (libsource (lib "easyedapro") (part "MAX9111ESA+T"))
    )
  )
  (nets
    (net (code "1") (name "ADI_5V") (class "Default")
      (node (ref "C14") (pin "1") (pinfunction "1_1") (pintype "input"))
      (node (ref "R20") (pin "1") (pinfunction "1_1") (pintype "input"))
      (node (ref "R22") (pin "2") (pinfunction "2_2") (pintype "input"))
      (node (ref "U5") (pin "14") (pinfunction "AN1/C2IN1+/RA1_14") (pintype "input"))
    )
    (net (code "2") (name "ADI_12V") (class "Default")
      (node (ref "C5") (pin "1") (pinfunction "1_1") (pintype "input"))
      (node (ref "R10") (pin "2") (pinfunction "2_2") (pintype "input"))
      (node (ref "R9") (pin "1") (pinfunction "1_1") (pintype "input"))
      (node (ref "U5") (pin "13") (pinfunction "AN0/OA2OUT/RA0_13") (pintype "input"))
    )
    (net (code "3") (name "ASW_EN") (class "Default")
      (node (ref "R16") (pin "1") (pinfunction "1_1") (pintype "input"))
      (node (ref "SW2") (pin "5") (pinfunction "5_5") (pintype "input"))
      (node (ref "U1") (pin "6") (pinfunction "E#_6") (pintype "unspecified"))
      (node (ref "U2") (pin "6") (pinfunction "E#_6") (pintype "unspecified"))
      (node (ref "U3") (pin "6") (pinfunction "E#_6") (pintype "unspecified"))
      (node (ref "U4") (pin "6") (pinfunction "E#_6") (pintype "unspecified"))
      (node (ref "U5") (pin "4") (pinfunction "RP118/RG6_4") (pintype "input"))
    )
    (net (code "4") (name "ASW_S0") (class "Default")
      (node (ref "R13") (pin "1") (pinfunction "1_1") (pintype "input"))
      (node (ref "SW2") (pin "8") (pinfunction "8_8") (pintype "input"))
      (node (ref "U1") (pin "11") (pinfunction "S0_11") (pintype "unspecified"))
      (node (ref "U2") (pin "11") (pinfunction "S0_11") (pintype "unspecified"))
      (node (ref "U3") (pin "11") (pinfunction "S0_11") (pintype "unspecified"))
      (node (ref "U4") (pin "11") (pinfunction "S0_11") (pintype "unspecified"))
      (node (ref "U5") (pin "1") (pinfunction "TDI/RA7_1") (pintype "input"))
    )
    (net (code "5") (name "ASW_S1") (class "Default")
      (node (ref "R14") (pin "1") (pinfunction "1_1") (pintype "input"))
      (node (ref "SW2") (pin "7") (pinfunction "7_7") (pintype "input"))
      (node (ref "U1") (pin "10") (pinfunction "S1_10") (pintype "unspecified"))
      (node (ref "U2") (pin "10") (pinfunction "S1_10") (pintype "unspecified"))
      (node (ref "U3") (pin "10") (pinfunction "S1_10") (pintype "unspecified"))
      (node (ref "U4") (pin "10") (pinfunction "S1_10") (pintype "unspecified"))
      (node (ref "U5") (pin "2") (pinfunction "RPI46/T3CK/RB14_2") (pintype "input"))
    )
    (net (code "6") (name "ASW_S2") (class "Default")
      (node (ref "R15") (pin "1") (pinfunction "1_1") (pintype "input"))
      (node (ref "SW2") (pin "6") (pinfunction "6_6") (pintype "input"))
      (node (ref "U1") (pin "9") (pinfunction "S2_9") (pintype "unspecified"))
      (node (ref "U2") (pin "9") (pinfunction "S2_9") (pintype "unspecified"))
      (node (ref "U3") (pin "9") (pinfunction "S2_9") (pintype "unspecified"))
      (node (ref "U4") (pin "9") (pinfunction "S2_9") (pintype "unspecified"))
      (node (ref "U5") (pin "3") (pinfunction "RPI47/T5CK/RB15_3") (pintype "input"))
    )
    (net (code "7") (name "FIB_RX0") (class "Default")
      (node (ref "R29") (pin "1") (pinfunction "1_1") (pintype "input"))
      (node (ref "U2") (pin "13") (pinfunction "Y0_13") (pintype "unspecified"))
    )
    (net (code "8") (name "FIB_RX0_CHK") (class "Default")
      (node (ref "R2") (pin "2") (pinfunction "2_2") (pintype "input"))
      (node (ref "U5") (pin "29") (pinfunction "AN14/RPI94/RE14_29") (pintype "input"))
    )
    (net (code "9") (name "FIB_RX0_IN") (class "Default")
      (node (ref "R2") (pin "1") (pinfunction "1_1") (pintype "input"))
      (node (ref "R5") (pin "1") (pinfunction "1_1") (pintype "input"))
      (node (ref "R58") (pin "2") (pinfunction "2_2") (pintype "input"))
      (node (ref "U10") (pin "7") (pinfunction "OUT_7") (pintype "unspecified"))
      (node (ref "U2") (pin "3") (pinfunction "Z_3") (pintype "unspecified"))
    )
    (net (code "10") (name "FIB_RX1") (class "Default")
      (node (ref "R33") (pin "1") (pinfunction "1_1") (pintype "input"))
      (node (ref "U4") (pin "13") (pinfunction "Y0_13") (pintype "unspecified"))
    )
    (net (code "11") (name "FIB_RX1_CHK") (class "Default")
      (node (ref "R1") (pin "2") (pinfunction "2_2") (pintype "input"))
      (node (ref "U5") (pin "30") (pinfunction "AN15/RPI95/RE15_30") (pintype "input"))
    )
    (net (code "12") (name "FIB_RX1_IN") (class "Default")
      (node (ref "R1") (pin "1") (pinfunction "1_1") (pintype "input"))
      (node (ref "R7") (pin "1") (pinfunction "1_1") (pintype "input"))
      (node (ref "R70") (pin "2") (pinfunction "2_2") (pintype "input"))
      (node (ref "U13") (pin "7") (pinfunction "OUT_7") (pintype "unspecified"))
      (node (ref "U4") (pin "3") (pinfunction "Z_3") (pintype "unspecified"))
    )
    (net (code "13") (name "FIB_RX2") (class "Default")
      (node (ref "R37") (pin "1") (pinfunction "1_1") (pintype "input"))
      (node (ref "U2") (pin "14") (pinfunction "Y1_14") (pintype "unspecified"))
    )
    (net (code "14") (name "FIB_RX3") (class "Default")
      (node (ref "R43") (pin "1") (pinfunction "1_1") (pintype "input"))
      (node (ref "U4") (pin "14") (pinfunction "Y1_14") (pintype "unspecified"))
    )
    (net (code "15") (name "FIB_RX4") (class "Default")
      (node (ref "R32") (pin "2") (pinfunction "2_2") (pintype "input"))
      (node (ref "U2") (pin "15") (pinfunction "Y2_15") (pintype "unspecified"))
    )
    (net (code "16") (name "FIB_RX5") (class "Default")
      (node (ref "R36") (pin "2") (pinfunction "2_2") (pintype "input"))
      (node (ref "U4") (pin "15") (pinfunction "Y2_15") (pintype "unspecified"))
    )
    (net (code "17") (name "FIB_RX6") (class "Default")
      (node (ref "R40") (pin "2") (pinfunction "2_2") (pintype "input"))
      (node (ref "U2") (pin "12") (pinfunction "Y3_12") (pintype "unspecified"))
    )
    (net (code "18") (name "FIB_RX7") (class "Default")
      (node (ref "R44") (pin "2") (pinfunction "2_2") (pintype "input"))
      (node (ref "U4") (pin "12") (pinfunction "Y3_12") (pintype "unspecified"))
    )
    (net (code "19") (name "FIB_RX_0") (class "Default")
      (node (ref "CON1") (pin "C16") (pinfunction "C16_C16") (pintype "input"))
      (node (ref "R29") (pin "2") (pinfunction "2_2") (pintype "input"))
    )
    (net (code "20") (name "FIB_RX_1") (class "Default")
      (node (ref "CON1") (pin "C18") (pinfunction "C18_C18") (pintype "input"))
      (node (ref "R33") (pin "2") (pinfunction "2_2") (pintype "input"))
    )
    (net (code "21") (name "FIB_RX_2") (class "Default")
      (node (ref "CON1") (pin "C20") (pinfunction "C20_C20") (pintype "input"))
      (node (ref "R37") (pin "2") (pinfunction "2_2") (pintype "input"))
    )
    (net (code "22") (name "FIB_RX_3") (class "Default")
      (node (ref "CON1") (pin "C22") (pinfunction "C22_C22") (pintype "input"))
      (node (ref "R43") (pin "2") (pinfunction "2_2") (pintype "input"))
    )
    (net (code "23") (name "FIB_RX_4") (class "Default")
      (node (ref "CON1") (pin "D16") (pinfunction "D16_D16") (pintype "input"))
      (node (ref "R32") (pin "1") (pinfunction "1_1") (pintype "input"))
    )
    (net (code "24") (name "FIB_RX_5") (class "Default")
      (node (ref "CON1") (pin "D18") (pinfunction "D18_D18") (pintype "input"))
      (node (ref "R36") (pin "1") (pinfunction "1_1") (pintype "input"))
    )
    (net (code "25") (name "FIB_RX_6") (class "Default")
      (node (ref "CON1") (pin "D20") (pinfunction "D20_D20") (pintype "input"))
      (node (ref "R40") (pin "1") (pinfunction "1_1") (pintype "input"))
    )
    (net (code "26") (name "FIB_RX_7") (class "Default")
      (node (ref "CON1") (pin "D22") (pinfunction "D22_D22") (pintype "input"))
      (node (ref "R44") (pin "1") (pinfunction "1_1") (pintype "input"))
    )
    (net (code "27") (name "FIB_TX0") (class "Default")
      (node (ref "R28") (pin "1") (pinfunction "1_1") (pintype "input"))
      (node (ref "U1") (pin "13") (pinfunction "Y0_13") (pintype "unspecified"))
    )
    (net (code "28") (name "FIB_TX0_CHK") (class "Default")
      (node (ref "R8") (pin "2") (pinfunction "2_2") (pintype "input"))
      (node (ref "U5") (pin "50") (pinfunction "RP54/RC6_50") (pintype "input"))
    )
    (net (code "29") (name "FIB_TX0_OUT") (class "Default")
      (node (ref "R57") (pin "1") (pinfunction "1_1") (pintype "input"))
      (node (ref "R6") (pin "1") (pinfunction "1_1") (pintype "input"))
      (node (ref "R69") (pin "1") (pinfunction "1_1") (pintype "input"))
      (node (ref "SW1") (pin "7") (pinfunction "7_7") (pintype "input"))
      (node (ref "SW1") (pin "8") (pinfunction "8_8") (pintype "input"))
      (node (ref "U12") (pin "2") (pinfunction "DIN_2") (pintype "unspecified"))
      (node (ref "U9") (pin "2") (pinfunction "DIN_2") (pintype "unspecified"))
    )
    (net (code "30") (name "FIB_TX0_SEL") (class "Default")
      (node (ref "R3") (pin "2") (pinfunction "2_2") (pintype "input"))
      (node (ref "SW1") (pin "1") (pinfunction "1_1") (pintype "input"))
    )
    (net (code "31") (name "FIB_TX1") (class "Default")
      (node (ref "R31") (pin "1") (pinfunction "1_1") (pintype "input"))
      (node (ref "U3") (pin "13") (pinfunction "Y0_13") (pintype "unspecified"))
    )
    (net (code "32") (name "FIB_TX1_CHK") (class "Default")
      (node (ref "R6") (pin "2") (pinfunction "2_2") (pintype "input"))
      (node (ref "U5") (pin "51") (pinfunction "RP55/RC7_51") (pintype "input"))
    )
    (net (code "33") (name "FIB_TX1_OUT") (class "Default")
      (node (ref "R8") (pin "1") (pinfunction "1_1") (pintype "input"))
      (node (ref "SW1") (pin "5") (pinfunction "5_5") (pintype "input"))
      (node (ref "SW1") (pin "6") (pinfunction "6_6") (pintype "input"))
    )
    (net (code "34") (name "FIB_TX1_SEL") (class "Default")
      (node (ref "R4") (pin "2") (pinfunction "2_2") (pintype "input"))
      (node (ref "SW1") (pin "3") (pinfunction "3_3") (pintype "input"))
    )
    (net (code "35") (name "FIB_TX2") (class "Default")
      (node (ref "R35") (pin "1") (pinfunction "1_1") (pintype "input"))
      (node (ref "U1") (pin "14") (pinfunction "Y1_14") (pintype "unspecified"))
    )
    (net (code "36") (name "FIB_TX3") (class "Default")
      (node (ref "R39") (pin "1") (pinfunction "1_1") (pintype "input"))
      (node (ref "U3") (pin "14") (pinfunction "Y1_14") (pintype "unspecified"))
    )
    (net (code "37") (name "FIB_TX4") (class "Default")
      (node (ref "R30") (pin "2") (pinfunction "2_2") (pintype "input"))
      (node (ref "U1") (pin "15") (pinfunction "Y2_15") (pintype "unspecified"))
    )
    (net (code "38") (name "FIB_TX5") (class "Default")
      (node (ref "R34") (pin "2") (pinfunction "2_2") (pintype "input"))
      (node (ref "U3") (pin "15") (pinfunction "Y2_15") (pintype "unspecified"))
    )
    (net (code "39") (name "FIB_TX6") (class "Default")
      (node (ref "R38") (pin "2") (pinfunction "2_2") (pintype "input"))
      (node (ref "U1") (pin "12") (pinfunction "Y3_12") (pintype "unspecified"))
    )
    (net (code "40") (name "FIB_TX7") (class "Default")
      (node (ref "R41") (pin "2") (pinfunction "2_2") (pintype "input"))
      (node (ref "U3") (pin "12") (pinfunction "Y3_12") (pintype "unspecified"))
    )
    (net (code "41") (name "FIB_TX_0") (class "Default")
      (node (ref "CON1") (pin "C15") (pinfunction "C15_C15") (pintype "input"))
      (node (ref "R28") (pin "2") (pinfunction "2_2") (pintype "input"))
    )
    (net (code "42") (name "FIB_TX_1") (class "Default")
      (node (ref "CON1") (pin "C17") (pinfunction "C17_C17") (pintype "input"))
      (node (ref "R31") (pin "2") (pinfunction "2_2") (pintype "input"))
    )
    (net (code "43") (name "FIB_TX_2") (class "Default")
      (node (ref "CON1") (pin "C19") (pinfunction "C19_C19") (pintype "input"))
      (node (ref "R35") (pin "2") (pinfunction "2_2") (pintype "input"))
    )
    (net (code "44") (name "FIB_TX_3") (class "Default")
      (node (ref "CON1") (pin "C21") (pinfunction "C21_C21") (pintype "input"))
      (node (ref "R39") (pin "2") (pinfunction "2_2") (pintype "input"))
    )
    (net (code "45") (name "FIB_TX_4") (class "Default")
      (node (ref "CON1") (pin "D15") (pinfunction "D15_D15") (pintype "input"))
      (node (ref "R30") (pin "1") (pinfunction "1_1") (pintype "input"))
    )
    (net (code "46") (name "FIB_TX_5") (class "Default")
      (node (ref "CON1") (pin "D17") (pinfunction "D17_D17") (pintype "input"))
      (node (ref "R34") (pin "1") (pinfunction "1_1") (pintype "input"))
    )
    (net (code "47") (name "FIB_TX_6") (class "Default")
      (node (ref "CON1") (pin "D19") (pinfunction "D19_D19") (pintype "input"))
      (node (ref "R38") (pin "1") (pinfunction "1_1") (pintype "input"))
    )
    (net (code "48") (name "FIB_TX_7") (class "Default")
      (node (ref "CON1") (pin "D21") (pinfunction "D21_D21") (pintype "input"))
      (node (ref "R41") (pin "1") (pinfunction "1_1") (pintype "input"))
    )
    (net (code "49") (name "GND") (class "Default")
      (node (ref "C1") (pin "1") (pinfunction "1_1") (pintype "input"))
      (node (ref "C10") (pin "2") (pinfunction "2_2") (pintype "input"))
      (node (ref "C11") (pin "2") (pinfunction "2_2") (pintype "input"))
      (node (ref "C12") (pin "2") (pinfunction "2_2") (pintype "input"))
      (node (ref "C13") (pin "2") (pinfunction "2_2") (pintype "input"))
      (node (ref "C14") (pin "2") (pinfunction "2_2") (pintype "input"))
      (node (ref "C15") (pin "2") (pinfunction "2_2") (pintype "input"))
      (node (ref "C16") (pin "2") (pinfunction "2_2") (pintype "input"))
      (node (ref "C17") (pin "2") (pinfunction "2_2") (pintype "input"))
      (node (ref "C18") (pin "2") (pinfunction "2_2") (pintype "input"))
      (node (ref "C19") (pin "2") (pinfunction "2_2") (pintype "input"))
      (node (ref "C2") (pin "1") (pinfunction "1_1") (pintype "input"))
      (node (ref "C20") (pin "2") (pinfunction "2_2") (pintype "input"))
      (node (ref "C21") (pin "2") (pinfunction "2_2") (pintype "input"))
      (node (ref "C22") (pin "2") (pinfunction "2_2") (pintype "input"))
      (node (ref "C23") (pin "1") (pinfunction "1_1") (pintype "input"))
      (node (ref "C24") (pin "1") (pinfunction "1_1") (pintype "input"))
      (node (ref "C25") (pin "1") (pinfunction "1_1") (pintype "input"))
      (node (ref "C26") (pin "1") (pinfunction "1_1") (pintype "input"))
      (node (ref "C27") (pin "1") (pinfunction "1_1") (pintype "input"))
      (node (ref "C28") (pin "2") (pinfunction "2_2") (pintype "input"))
      (node (ref "C29") (pin "2") (pinfunction "2_2") (pintype "input"))
      (node (ref "C3") (pin "1") (pinfunction "1_1") (pintype "input"))
      (node (ref "C30") (pin "2") (pinfunction "2_2") (pintype "input"))
      (node (ref "C31") (pin "2") (pinfunction "2_2") (pintype "input"))
      (node (ref "C32") (pin "2") (pinfunction "2_2") (pintype "input"))
      (node (ref "C33") (pin "2") (pinfunction "2_2") (pintype "input"))
      (node (ref "C34") (pin "2") (pinfunction "2_2") (pintype "input"))
      (node (ref "C35") (pin "2") (pinfunction "2_2") (pintype "input"))
      (node (ref "C36") (pin "2") (pinfunction "2_2") (pintype "input"))
      (node (ref "C37") (pin "2") (pinfunction "2_2") (pintype "input"))
      (node (ref "C38") (pin "2") (pinfunction "2_2") (pintype "input"))
      (node (ref "C39") (pin "2") (pinfunction "2_2") (pintype "input"))
      (node (ref "C4") (pin "1") (pinfunction "1_1") (pintype "input"))
      (node (ref "C40") (pin "2") (pinfunction "2_2") (pintype "input"))
      (node (ref "C41") (pin "2") (pinfunction "2_2") (pintype "input"))
      (node (ref "C42") (pin "2") (pinfunction "2_2") (pintype "input"))
      (node (ref "C43") (pin "2") (pinfunction "2_2") (pintype "input"))
      (node (ref "C5") (pin "2") (pinfunction "2_2") (pintype "input"))
      (node (ref "C6") (pin "2") (pinfunction "2_2") (pintype "input"))
      (node (ref "C7") (pin "2") (pinfunction "2_2") (pintype "input"))
      (node (ref "C8") (pin "2") (pinfunction "2_2") (pintype "input"))
      (node (ref "C9") (pin "1") (pinfunction "1_1") (pintype "input"))
      (node (ref "CN1") (pin "3") (pinfunction "3_3") (pintype "input"))
      (node (ref "CON1") (pin "A4") (pinfunction "A4_A4") (pintype "input"))
      (node (ref "CON1") (pin "A8") (pinfunction "A8_A8") (pintype "input"))
      (node (ref "CON1") (pin "B4") (pinfunction "B4_B4") (pintype "input"))
      (node (ref "CON1") (pin "B8") (pinfunction "B8_B8") (pintype "input"))
      (node (ref "CON1") (pin "C4") (pinfunction "C4_C4") (pintype "input"))
      (node (ref "CON1") (pin "C8") (pinfunction "C8_C8") (pintype "input"))
      (node (ref "CON1") (pin "D4") (pinfunction "D4_D4") (pintype "input"))
      (node (ref "CON1") (pin "D8") (pinfunction "D8_D8") (pintype "input"))
      (node (ref "CON1") (pin "E4") (pinfunction "E4_E4") (pintype "input"))
      (node (ref "CON1") (pin "E8") (pinfunction "E8_E8") (pintype "input"))
      (node (ref "CON1") (pin "F1") (pinfunction "F1_F1") (pintype "input"))
      (node (ref "CON1") (pin "F10") (pinfunction "F10_F10") (pintype "input"))
      (node (ref "CON1") (pin "F11") (pinfunction "F11_F11") (pintype "input"))
      (node (ref "CON1") (pin "F12") (pinfunction "F12_F12") (pintype "input"))
      (node (ref "CON1") (pin "F13") (pinfunction "F13_F13") (pintype "input"))
      (node (ref "CON1") (pin "F14") (pinfunction "F14_F14") (pintype "input"))
      (node (ref "CON1") (pin "F15") (pinfunction "F15_F15") (pintype "input"))
      (node (ref "CON1") (pin "F16") (pinfunction "F16_F16") (pintype "input"))
      (node (ref "CON1") (pin "F17") (pinfunction "F17_F17") (pintype "input"))
      (node (ref "CON1") (pin "F18") (pinfunction "F18_F18") (pintype "input"))
      (node (ref "CON1") (pin "F19") (pinfunction "F19_F19") (pintype "input"))
      (node (ref "CON1") (pin "F2") (pinfunction "F2_F2") (pintype "input"))
      (node (ref "CON1") (pin "F20") (pinfunction "F20_F20") (pintype "input"))
      (node (ref "CON1") (pin "F21") (pinfunction "F21_F21") (pintype "input"))
      (node (ref "CON1") (pin "F22") (pinfunction "F22_F22") (pintype "input"))
      (node (ref "CON1") (pin "F23") (pinfunction "F23_F23") (pintype "input"))
      (node (ref "CON1") (pin "F24") (pinfunction "F24_F24") (pintype "input"))
      (node (ref "CON1") (pin "F25") (pinfunction "F25_F25") (pintype "input"))
      (node (ref "CON1") (pin "F3") (pinfunction "F3_F3") (pintype "input"))
      (node (ref "CON1") (pin "F4") (pinfunction "F4_F4") (pintype "input"))
      (node (ref "CON1") (pin "F5") (pinfunction "F5_F5") (pintype "input"))
      (node (ref "CON1") (pin "F6") (pinfunction "F6_F6") (pintype "input"))
      (node (ref "CON1") (pin "F7") (pinfunction "F7_F7") (pintype "input"))
      (node (ref "CON1") (pin "F8") (pinfunction "F8_F8") (pintype "input"))
      (node (ref "CON1") (pin "F9") (pinfunction "F9_F9") (pintype "input"))
      (node (ref "CON2") (pin "F1") (pinfunction "F1_F1") (pintype "input"))
      (node (ref "CON2") (pin "F10") (pinfunction "F10_F10") (pintype "input"))
      (node (ref "CON2") (pin "F11") (pinfunction "F11_F11") (pintype "input"))
      (node (ref "CON2") (pin "F12") (pinfunction "F12_F12") (pintype "input"))
      (node (ref "CON2") (pin "F13") (pinfunction "F13_F13") (pintype "input"))
      (node (ref "CON2") (pin "F14") (pinfunction "F14_F14") (pintype "input"))
      (node (ref "CON2") (pin "F15") (pinfunction "F15_F15") (pintype "input"))
      (node (ref "CON2") (pin "F16") (pinfunction "F16_F16") (pintype "input"))
      (node (ref "CON2") (pin "F17") (pinfunction "F17_F17") (pintype "input"))
      (node (ref "CON2") (pin "F18") (pinfunction "F18_F18") (pintype "input"))
      (node (ref "CON2") (pin "F19") (pinfunction "F19_F19") (pintype "input"))
      (node (ref "CON2") (pin "F2") (pinfunction "F2_F2") (pintype "input"))
      (node (ref "CON2") (pin "F20") (pinfunction "F20_F20") (pintype "input"))
      (node (ref "CON2") (pin "F21") (pinfunction "F21_F21") (pintype "input"))
      (node (ref "CON2") (pin "F22") (pinfunction "F22_F22") (pintype "input"))
      (node (ref "CON2") (pin "F3") (pinfunction "F3_F3") (pintype "input"))
      (node (ref "CON2") (pin "F4") (pinfunction "F4_F4") (pintype "input"))
      (node (ref "CON2") (pin "F5") (pinfunction "F5_F5") (pintype "input"))
      (node (ref "CON2") (pin "F6") (pinfunction "F6_F6") (pintype "input"))
      (node (ref "CON2") (pin "F7") (pinfunction "F7_F7") (pintype "input"))
      (node (ref "CON2") (pin "F8") (pinfunction "F8_F8") (pintype "input"))
      (node (ref "CON2") (pin "F9") (pinfunction "F9_F9") (pintype "input"))
      (node (ref "R10") (pin "1") (pinfunction "1_1") (pintype "input"))
      (node (ref "R17") (pin "2") (pinfunction "2_2") (pintype "input"))
      (node (ref "R18") (pin "2") (pinfunction "2_2") (pintype "input"))
      (node (ref "R22") (pin "1") (pinfunction "1_1") (pintype "input"))
      (node (ref "R27") (pin "2") (pinfunction "2_2") (pintype "input"))
      (node (ref "R59") (pin "1") (pinfunction "1_1") (pintype "input"))
      (node (ref "R60") (pin "1") (pinfunction "1_1") (pintype "input"))
      (node (ref "R61") (pin "1") (pinfunction "1_1") (pintype "input"))
      (node (ref "R62") (pin "1") (pinfunction "1_1") (pintype "input"))
      (node (ref "R63") (pin "1") (pinfunction "1_1") (pintype "input"))
      (node (ref "R71") (pin "1") (pinfunction "1_1") (pintype "input"))
      (node (ref "R72") (pin "1") (pinfunction "1_1") (pintype "input"))
      (node (ref "R73") (pin "1") (pinfunction "1_1") (pintype "input"))
      (node (ref "R74") (pin "1") (pinfunction "1_1") (pintype "input"))
      (node (ref "R75") (pin "1") (pinfunction "1_1") (pintype "input"))
      (node (ref "SW2") (pin "1") (pinfunction "1_1") (pintype "input"))
      (node (ref "SW2") (pin "2") (pinfunction "2_2") (pintype "input"))
      (node (ref "SW2") (pin "3") (pinfunction "3_3") (pintype "input"))
      (node (ref "SW2") (pin "4") (pinfunction "4_4") (pintype "input"))
      (node (ref "SW3") (pin "1") (pinfunction "1_1") (pintype "input"))
      (node (ref "SW3") (pin "2") (pinfunction "2_2") (pintype "input"))
      (node (ref "SW3") (pin "3") (pinfunction "3_3") (pintype "input"))
      (node (ref "SW3") (pin "4") (pinfunction "4_4") (pintype "input"))
      (node (ref "U1") (pin "7") (pinfunction "VEE_7") (pintype "unspecified"))
      (node (ref "U1") (pin "8") (pinfunction "GND_8") (pintype "unspecified"))
      (node (ref "U10") (pin "5") (pinfunction "GND_5") (pintype "unspecified"))
      (node (ref "U11") (pin "1") (pinfunction "RX_GND_1") (pintype "input"))
      (node (ref "U11") (pin "9") (pinfunction "TX_GND_9") (pintype "input"))
      (node (ref "U12") (pin "4") (pinfunction "GND_4") (pintype "unspecified"))
      (node (ref "U13") (pin "5") (pinfunction "GND_5") (pintype "unspecified"))
      (node (ref "U2") (pin "7") (pinfunction "VEE_7") (pintype "unspecified"))
      (node (ref "U2") (pin "8") (pinfunction "GND_8") (pintype "unspecified"))
      (node (ref "U3") (pin "7") (pinfunction "VEE_7") (pintype "unspecified"))
      (node (ref "U3") (pin "8") (pinfunction "GND_8") (pintype "unspecified"))
      (node (ref "U4") (pin "7") (pinfunction "VEE_7") (pintype "unspecified"))
      (node (ref "U4") (pin "8") (pinfunction "GND_8") (pintype "unspecified"))
      (node (ref "U5") (pin "20") (pinfunction "AVSS_20") (pintype "input"))
      (node (ref "U5") (pin "25") (pinfunction "Vss_25") (pintype "input"))
      (node (ref "U5") (pin "41") (pinfunction "VSS_41") (pintype "input"))
      (node (ref "U5") (pin "9") (pinfunction "Vss_9") (pintype "input"))
      (node (ref "U6") (pin "5") (pinfunction "GND_5") (pintype "input"))
      (node (ref "U7") (pin "4") (pinfunction "PGND_4") (pintype "unspecified"))
      (node (ref "U7") (pin "6") (pinfunction "AGND_6") (pintype "unspecified"))
      (node (ref "U8") (pin "1") (pinfunction "RX_GND_1") (pintype "input"))
      (node (ref "U8") (pin "9") (pinfunction "TX_GND_9") (pintype "input"))
      (node (ref "U9") (pin "4") (pinfunction "GND_4") (pintype "unspecified"))
    )
    (net (code "50") (name "LED_B") (class "Default")
      (node (ref "R25") (pin "2") (pinfunction "2_2") (pintype "input"))
      (node (ref "U5") (pin "62") (pinfunction "RPI44/RB12_62") (pintype "input"))
    )
    (net (code "51") (name "LED_G") (class "Default")
      (node (ref "R24") (pin "2") (pinfunction "2_2") (pintype "input"))
      (node (ref "U5") (pin "63") (pinfunction "RPI45/CTPLS/RB13_63") (pintype "input"))
    )
    (net (code "52") (name "LED_R") (class "Default")
      (node (ref "R23") (pin "2") (pinfunction "2_2") (pintype "input"))
      (node (ref "U5") (pin "64") (pinfunction "TDO/RA10_64") (pintype "input"))
    )
    (net (code "53") (name "MCLR") (class "Default")
      (node (ref "CN1") (pin "5") (pinfunction "5_5") (pintype "input"))
      (node (ref "R11") (pin "2") (pinfunction "2_2") (pintype "input"))
      (node (ref "U5") (pin "7") (pinfunction "#MCLR_7") (pintype "input"))
    )
    (net (code "54") (name "Net-(C7-Pad1)") (class "Default")
      (node (ref "C7") (pin "1") (pinfunction "1_1") (pintype "input"))
      (node (ref "R11") (pin "1") (pinfunction "1_1") (pintype "input"))
      (node (ref "R12") (pin "2") (pinfunction "2_2") (pintype "input"))
    )
    (net (code "55") (name "Net-(LED1-KB)") (class "Default")
      (node (ref "LED1") (pin "4") (pinfunction "KB_4") (pintype "input"))
      (node (ref "R25") (pin "1") (pinfunction "1_1") (pintype "input"))
    )
    (net (code "56") (name "Net-(LED1-KG)") (class "Default")
      (node (ref "LED1") (pin "3") (pinfunction "KG_3") (pintype "input"))
      (node (ref "R24") (pin "1") (pinfunction "1_1") (pintype "input"))
    )
    (net (code "57") (name "Net-(LED1-KR)") (class "Default")
      (node (ref "LED1") (pin "1") (pinfunction "KR_1") (pintype "input"))
      (node (ref "R23") (pin "1") (pinfunction "1_1") (pintype "input"))
    )
    (net (code "58") (name "Net-(R5-Pad2)") (class "Default")
      (node (ref "R5") (pin "2") (pinfunction "2_2") (pintype "input"))
      (node (ref "SW1") (pin "2") (pinfunction "2_2") (pintype "input"))
    )
    (net (code "59") (name "Net-(R7-Pad2)") (class "Default")
      (node (ref "R7") (pin "2") (pinfunction "2_2") (pintype "input"))
      (node (ref "SW1") (pin "4") (pinfunction "4_4") (pintype "input"))
    )
    (net (code "60") (name "Net-(U1-Z)") (class "Default")
      (node (ref "R3") (pin "1") (pinfunction "1_1") (pintype "input"))
      (node (ref "U1") (pin "3") (pinfunction "Z_3") (pintype "unspecified"))
    )
    (net (code "61") (name "Net-(U3-Z)") (class "Default")
      (node (ref "R4") (pin "1") (pinfunction "1_1") (pintype "input"))
      (node (ref "U3") (pin "3") (pinfunction "Z_3") (pintype "unspecified"))
    )
    (net (code "62") (name "Net-(U5-Vcap)") (class "Default")
      (node (ref "C9") (pin "2") (pinfunction "2_2") (pintype "input"))
      (node (ref "U5") (pin "56") (pinfunction "Vcap_56") (pintype "input"))
    )
    (net (code "63") (name "Net-(U7-FB)") (class "Default")
      (node (ref "R26") (pin "2") (pinfunction "2_2") (pintype "input"))
      (node (ref "R27") (pin "1") (pinfunction "1_1") (pintype "input"))
      (node (ref "U7") (pin "7") (pinfunction "FB_7") (pintype "unspecified"))
    )
    (net (code "64") (name "Net-(U7-SW)") (class "Default")
      (node (ref "L1") (pin "1") (pinfunction "1_1") (pintype "input"))
      (node (ref "U7") (pin "3") (pinfunction "SW_3") (pintype "unspecified"))
    )
    (net (code "65") (name "Net-(U8-RX_VCC)") (class "Default")
      (node (ref "C32") (pin "1") (pinfunction "1_1") (pintype "input"))
      (node (ref "C34") (pin "1") (pinfunction "1_1") (pintype "input"))
      (node (ref "L2") (pin "1") (pinfunction "1_1") (pintype "input"))
      (node (ref "U8") (pin "5") (pinfunction "RX_VCC_5") (pintype "input"))
    )
    (net (code "66") (name "Net-(U8-SD)") (class "Default")
      (node (ref "R63") (pin "2") (pinfunction "2_2") (pintype "input"))
      (node (ref "U8") (pin "4") (pinfunction "SD_4") (pintype "input"))
    )
    (net (code "67") (name "Net-(U8-TX+)") (class "Default")
      (node (ref "R54") (pin "1") (pinfunction "1_1") (pintype "input"))
      (node (ref "R56") (pin "1") (pinfunction "1_1") (pintype "input"))
      (node (ref "R61") (pin "2") (pinfunction "2_2") (pintype "input"))
      (node (ref "U8") (pin "8") (pinfunction "TX+_8") (pintype "input"))
      (node (ref "U9") (pin "7") (pinfunction "DO+_7") (pintype "unspecified"))
    )
    (net (code "68") (name "Net-(U8-TX-)") (class "Default")
      (node (ref "R55") (pin "1") (pinfunction "1_1") (pintype "input"))
      (node (ref "R56") (pin "2") (pinfunction "2_2") (pintype "input"))
      (node (ref "R62") (pin "2") (pinfunction "2_2") (pintype "input"))
      (node (ref "U8") (pin "7") (pinfunction "TX-_7") (pintype "input"))
      (node (ref "U9") (pin "8") (pinfunction "DO-_8") (pintype "unspecified"))
    )
    (net (code "69") (name "Net-(U8-TX_VCC)") (class "Default")
      (node (ref "C33") (pin "1") (pinfunction "1_1") (pintype "input"))
      (node (ref "C35") (pin "1") (pinfunction "1_1") (pintype "input"))
      (node (ref "L3") (pin "1") (pinfunction "1_1") (pintype "input"))
      (node (ref "U8") (pin "6") (pinfunction "TX_VCC_6") (pintype "input"))
    )
    (net (code "70") (name "Net-(U10-IN+)") (class "Default")
      (node (ref "R53") (pin "1") (pinfunction "1_1") (pintype "input"))
      (node (ref "R60") (pin "2") (pinfunction "2_2") (pintype "input"))
      (node (ref "U10") (pin "2") (pinfunction "IN+_2") (pintype "unspecified"))
      (node (ref "U8") (pin "2") (pinfunction "RX+_2") (pintype "input"))
    )
    (net (code "71") (name "Net-(U10-IN-)") (class "Default")
      (node (ref "R52") (pin "1") (pinfunction "1_1") (pintype "input"))
      (node (ref "R59") (pin "2") (pinfunction "2_2") (pintype "input"))
      (node (ref "U10") (pin "1") (pinfunction "IN-_1") (pintype "unspecified"))
      (node (ref "U8") (pin "3") (pinfunction "RX-_3") (pintype "input"))
    )
    (net (code "72") (name "Net-(U11-RX+)") (class "Default")
      (node (ref "R65") (pin "1") (pinfunction "1_1") (pintype "input"))
      (node (ref "R72") (pin "2") (pinfunction "2_2") (pintype "input"))
      (node (ref "U11") (pin "2") (pinfunction "RX+_2") (pintype "input"))
      (node (ref "U13") (pin "2") (pinfunction "IN+_2") (pintype "unspecified"))
    )
    (net (code "73") (name "Net-(U11-RX-)") (class "Default")
      (node (ref "R64") (pin "1") (pinfunction "1_1") (pintype "input"))
      (node (ref "R71") (pin "2") (pinfunction "2_2") (pintype "input"))
      (node (ref "U11") (pin "3") (pinfunction "RX-_3") (pintype "input"))
      (node (ref "U13") (pin "1") (pinfunction "IN-_1") (pintype "unspecified"))
    )
    (net (code "74") (name "Net-(U11-RX_VCC)") (class "Default")
      (node (ref "C40") (pin "1") (pinfunction "1_1") (pintype "input"))
      (node (ref "C42") (pin "1") (pinfunction "1_1") (pintype "input"))
      (node (ref "L4") (pin "1") (pinfunction "1_1") (pintype "input"))
      (node (ref "U11") (pin "5") (pinfunction "RX_VCC_5") (pintype "input"))
    )
    (net (code "75") (name "Net-(U11-SD)") (class "Default")
      (node (ref "R75") (pin "2") (pinfunction "2_2") (pintype "input"))
      (node (ref "U11") (pin "4") (pinfunction "SD_4") (pintype "input"))
    )
    (net (code "76") (name "Net-(U11-TX+)") (class "Default")
      (node (ref "R66") (pin "1") (pinfunction "1_1") (pintype "input"))
      (node (ref "R68") (pin "1") (pinfunction "1_1") (pintype "input"))
      (node (ref "R73") (pin "2") (pinfunction "2_2") (pintype "input"))
      (node (ref "U11") (pin "8") (pinfunction "TX+_8") (pintype "input"))
      (node (ref "U12") (pin "7") (pinfunction "DO+_7") (pintype "unspecified"))
    )
    (net (code "77") (name "Net-(U11-TX-)") (class "Default")
      (node (ref "R67") (pin "1") (pinfunction "1_1") (pintype "input"))
      (node (ref "R68") (pin "2") (pinfunction "2_2") (pintype "input"))
      (node (ref "R74") (pin "2") (pinfunction "2_2") (pintype "input"))
      (node (ref "U11") (pin "7") (pinfunction "TX-_7") (pintype "input"))
      (node (ref "U12") (pin "8") (pinfunction "DO-_8") (pintype "unspecified"))
    )
    (net (code "78") (name "Net-(U11-TX_VCC)") (class "Default")
      (node (ref "C41") (pin "1") (pinfunction "1_1") (pintype "input"))
      (node (ref "C43") (pin "1") (pinfunction "1_1") (pintype "input"))
      (node (ref "L5") (pin "1") (pinfunction "1_1") (pintype "input"))
      (node (ref "U11") (pin "6") (pinfunction "TX_VCC_6") (pintype "input"))
    )
    (net (code "79") (name "PGC") (class "Default")
      (node (ref "CN1") (pin "1") (pinfunction "1_1") (pintype "input"))
      (node (ref "U5") (pin "17") (pinfunction "PGEC1/AN4/C11N1+/RPI34/RB2_17") (pintype "input"))
    )
    (net (code "80") (name "PGD") (class "Default")
      (node (ref "CN1") (pin "2") (pinfunction "2_2") (pintype "input"))
      (node (ref "U5") (pin "18") (pinfunction "PGED1/AN5/C1IN1-/RP35/RB3_18") (pintype "input"))
    )
    (net (code "81") (name "POW_5V") (class "Default")
      (node (ref "CON1") (pin "A10") (pinfunction "A10_A10") (pintype "input"))
      (node (ref "CON1") (pin "A11") (pinfunction "A11_A11") (pintype "input"))
      (node (ref "CON1") (pin "A9") (pinfunction "A9_A9") (pintype "input"))
      (node (ref "CON1") (pin "B10") (pinfunction "B10_B10") (pintype "input"))
      (node (ref "CON1") (pin "B11") (pinfunction "B11_B11") (pintype "input"))
      (node (ref "CON1") (pin "B9") (pinfunction "B9_B9") (pintype "input"))
      (node (ref "CON1") (pin "C10") (pinfunction "C10_C10") (pintype "input"))
      (node (ref "CON1") (pin "C11") (pinfunction "C11_C11") (pintype "input"))
      (node (ref "CON1") (pin "C9") (pinfunction "C9_C9") (pintype "input"))
      (node (ref "CON1") (pin "D10") (pinfunction "D10_D10") (pintype "input"))
      (node (ref "CON1") (pin "D11") (pinfunction "D11_D11") (pintype "input"))
      (node (ref "CON1") (pin "D9") (pinfunction "D9_D9") (pintype "input"))
      (node (ref "CON1") (pin "E10") (pinfunction "E10_E10") (pintype "input"))
      (node (ref "CON1") (pin "E11") (pinfunction "E11_E11") (pintype "input"))
      (node (ref "CON1") (pin "E9") (pinfunction "E9_E9") (pintype "input"))
      (node (ref "F2") (pin "2") (pinfunction "2_2") (pintype "input"))
    )
    (net (code "82") (name "POW_12V") (class "Default")
      (node (ref "CON1") (pin "A1") (pinfunction "A1_A1") (pintype "input"))
      (node (ref "CON1") (pin "A2") (pinfunction "A2_A2") (pintype "input"))
      (node (ref "CON1") (pin "A3") (pinfunction "A3_A3") (pintype "input"))
      (node (ref "CON1") (pin "B1") (pinfunction "B1_B1") (pintype "input"))
      (node (ref "CON1") (pin "B2") (pinfunction "B2_B2") (pintype "input"))
      (node (ref "CON1") (pin "B3") (pinfunction "B3_B3") (pintype "input"))
      (node (ref "CON1") (pin "C1") (pinfunction "C1_C1") (pintype "input"))
      (node (ref "CON1") (pin "C2") (pinfunction "C2_C2") (pintype "input"))
      (node (ref "CON1") (pin "C3") (pinfunction "C3_C3") (pintype "input"))
      (node (ref "CON1") (pin "D1") (pinfunction "D1_D1") (pintype "input"))
      (node (ref "CON1") (pin "D2") (pinfunction "D2_D2") (pintype "input"))
      (node (ref "CON1") (pin "D3") (pinfunction "D3_D3") (pintype "input"))
      (node (ref "CON1") (pin "E1") (pinfunction "E1_E1") (pintype "input"))
      (node (ref "CON1") (pin "E2") (pinfunction "E2_E2") (pintype "input"))
      (node (ref "CON1") (pin "E3") (pinfunction "E3_E3") (pintype "input"))
      (node (ref "F1") (pin "2") (pinfunction "2_2") (pintype "input"))
    )
    (net (code "83") (name "RS485_BUS_N") (class "Default")
      (node (ref "CON2") (pin "E18") (pinfunction "E18_E18") (pintype "input"))
      (node (ref "R51") (pin "2") (pinfunction "2_2") (pintype "input"))
    )
    (net (code "84") (name "RS485_BUS_P") (class "Default")
      (node (ref "CON2") (pin "E17") (pinfunction "E17_E17") (pintype "input"))
      (node (ref "R50") (pin "2") (pinfunction "2_2") (pintype "input"))
    )
    (net (code "85") (name "RS485_DE") (class "Default")
      (node (ref "R18") (pin "1") (pinfunction "1_1") (pintype "input"))
      (node (ref "U5") (pin "59") (pinfunction "RP97/RF1_59") (pintype "input"))
      (node (ref "U6") (pin "2") (pinfunction "RE#_2") (pintype "input"))
      (node (ref "U6") (pin "3") (pinfunction "DE_3") (pintype "input"))
    )
    (net (code "86") (name "RS485_DI") (class "Default")
      (node (ref "U5") (pin "61") (pinfunction "RP43/RB11_61") (pintype "input"))
      (node (ref "U6") (pin "4") (pinfunction "DI_4") (pintype "input"))
    )
    (net (code "87") (name "RS485_RO") (class "Default")
      (node (ref "U5") (pin "60") (pinfunction "RP42/RB10_60") (pintype "input"))
      (node (ref "U6") (pin "1") (pinfunction "RO_1") (pintype "input"))
    )
    (net (code "88") (name "RS485_S0_N") (class "Default")
      (node (ref "R17") (pin "1") (pinfunction "1_1") (pintype "input"))
      (node (ref "R19") (pin "1") (pinfunction "1_1") (pintype "input"))
      (node (ref "R51") (pin "1") (pinfunction "1_1") (pintype "input"))
      (node (ref "U6") (pin "7") (pinfunction "B_7") (pintype "input"))
    )
    (net (code "89") (name "RS485_S0_P") (class "Default")
      (node (ref "R19") (pin "2") (pinfunction "2_2") (pintype "input"))
      (node (ref "R21") (pin "2") (pinfunction "2_2") (pintype "input"))
      (node (ref "R50") (pin "1") (pinfunction "1_1") (pintype "input"))
      (node (ref "U6") (pin "6") (pinfunction "A_6") (pintype "input"))
    )
    (net (code "90") (name "SLOTSW_S0") (class "Default")
      (node (ref "R48") (pin "2") (pinfunction "2_2") (pintype "input"))
      (node (ref "U5") (pin "39") (pinfunction "OSC1/CLKI/RC12_39") (pintype "input"))
    )
    (net (code "91") (name "SLOTSW_S1") (class "Default")
      (node (ref "R46") (pin "2") (pinfunction "2_2") (pintype "input"))
      (node (ref "U5") (pin "40") (pinfunction "OSC2/CLKO/RC15_40") (pintype "input"))
    )
    (net (code "92") (name "SLOTSW_S2") (class "Default")
      (node (ref "R45") (pin "2") (pinfunction "2_2") (pintype "input"))
      (node (ref "U5") (pin "42") (pinfunction "RD8_42") (pintype "input"))
    )
    (net (code "93") (name "SLOTSW_S3") (class "Default")
      (node (ref "R42") (pin "2") (pinfunction "2_2") (pintype "input"))
      (node (ref "U5") (pin "43") (pinfunction "PGED2/ASDA2/RP37/RB5_43") (pintype "input"))
    )
    (net (code "94") (name "SLOT_SW0") (class "Default")
      (node (ref "CON2") (pin "D22") (pinfunction "D22_D22") (pintype "input"))
      (node (ref "R48") (pin "1") (pinfunction "1_1") (pintype "input"))
    )
    (net (code "95") (name "SLOT_SW1") (class "Default")
      (node (ref "CON2") (pin "D21") (pinfunction "D21_D21") (pintype "input"))
      (node (ref "R46") (pin "1") (pinfunction "1_1") (pintype "input"))
    )
    (net (code "96") (name "SLOT_SW2") (class "Default")
      (node (ref "CON2") (pin "D20") (pinfunction "D20_D20") (pintype "input"))
      (node (ref "R45") (pin "1") (pinfunction "1_1") (pintype "input"))
    )
    (net (code "97") (name "SLOT_SW3") (class "Default")
      (node (ref "CON2") (pin "D19") (pinfunction "D19_D19") (pintype "input"))
      (node (ref "R42") (pin "1") (pinfunction "1_1") (pintype "input"))
    )
    (net (code "98") (name "SWS4") (class "Default")
      (node (ref "SW3") (pin "8") (pinfunction "8_8") (pintype "input"))
      (node (ref "U5") (pin "5") (pinfunction "RPI119/RG7_5") (pintype "input"))
    )
    (net (code "99") (name "SWS5") (class "Default")
      (node (ref "SW3") (pin "7") (pinfunction "7_7") (pintype "input"))
      (node (ref "U5") (pin "6") (pinfunction "RP120/RG8_6") (pintype "input"))
    )
    (net (code "100") (name "SWS6") (class "Default")
      (node (ref "SW3") (pin "6") (pinfunction "6_6") (pintype "input"))
      (node (ref "U5") (pin "8") (pinfunction "RPI121/RG9_8") (pintype "input"))
    )
    (net (code "101") (name "SWS7") (class "Default")
      (node (ref "SW3") (pin "5") (pinfunction "5_5") (pintype "input"))
      (node (ref "U5") (pin "11") (pinfunction "AN10/RPI28/RA12_11") (pintype "input"))
    )
    (net (code "102") (name "TP1") (class "Default")
      (node (ref "TP1") (pin "1") (pinfunction "1_1") (pintype "input"))
      (node (ref "U5") (pin "31") (pinfunction "SDA2/RPI24/RA8_31") (pintype "input"))
    )
    (net (code "103") (name "TP2") (class "Default")
      (node (ref "TP2") (pin "1") (pinfunction "1_1") (pintype "input"))
      (node (ref "U5") (pin "32") (pinfunction "SCL2/RP36/RB4_32") (pintype "input"))
    )
    (net (code "104") (name "TP3") (class "Default")
      (node (ref "TP3") (pin "1") (pinfunction "1_1") (pintype "input"))
      (node (ref "U5") (pin "33") (pinfunction "CVREF2O/SDO1/RP20/T1CK/RA4_33") (pintype "input"))
    )
    (net (code "105") (name "TP4") (class "Default")
      (node (ref "TP4") (pin "1") (pinfunction "1_1") (pintype "input"))
      (node (ref "U5") (pin "34") (pinfunction "SDI1/RPI25/RA9_34") (pintype "input"))
    )
    (net (code "106") (name "VCC") (class "Default")
      (node (ref "C1") (pin "2") (pinfunction "2_2") (pintype "input"))
      (node (ref "C10") (pin "1") (pinfunction "1_1") (pintype "input"))
      (node (ref "C11") (pin "1") (pinfunction "1_1") (pintype "input"))
      (node (ref "C12") (pin "1") (pinfunction "1_1") (pintype "input"))
      (node (ref "C13") (pin "1") (pinfunction "1_1") (pintype "input"))
      (node (ref "C2") (pin "2") (pinfunction "2_2") (pintype "input"))
      (node (ref "C3") (pin "2") (pinfunction "2_2") (pintype "input"))
      (node (ref "C4") (pin "2") (pinfunction "2_2") (pintype "input"))
      (node (ref "C6") (pin "1") (pinfunction "1_1") (pintype "input"))
      (node (ref "C8") (pin "1") (pinfunction "1_1") (pintype "input"))
      (node (ref "CN1") (pin "4") (pinfunction "4_4") (pintype "input"))
      (node (ref "LED1") (pin "2") (pinfunction "CA_2") (pintype "input"))
      (node (ref "R12") (pin "1") (pinfunction "1_1") (pintype "input"))
      (node (ref "R13") (pin "2") (pinfunction "2_2") (pintype "input"))
      (node (ref "R14") (pin "2") (pinfunction "2_2") (pintype "input"))
      (node (ref "R15") (pin "2") (pinfunction "2_2") (pintype "input"))
      (node (ref "R16") (pin "2") (pinfunction "2_2") (pintype "input"))
      (node (ref "R21") (pin "1") (pinfunction "1_1") (pintype "input"))
      (node (ref "R47") (pin "2") (pinfunction "2_2") (pintype "input"))
      (node (ref "U1") (pin "16") (pinfunction "VCC_16") (pintype "unspecified"))
      (node (ref "U2") (pin "16") (pinfunction "VCC_16") (pintype "unspecified"))
      (node (ref "U3") (pin "16") (pinfunction "VCC_16") (pintype "unspecified"))
      (node (ref "U4") (pin "16") (pinfunction "VCC_16") (pintype "unspecified"))
      (node (ref "U5") (pin "10") (pinfunction "Vdd_10") (pintype "input"))
      (node (ref "U5") (pin "19") (pinfunction "AVDD_19") (pintype "input"))
      (node (ref "U5") (pin "26") (pinfunction "Vdd_26") (pintype "input"))
      (node (ref "U5") (pin "38") (pinfunction "Vdd_38") (pintype "input"))
      (node (ref "U5") (pin "57") (pinfunction "Vdd_57") (pintype "input"))
      (node (ref "U6") (pin "8") (pinfunction "VCC_8") (pintype "input"))
    )
    (net (code "107") (name "VCCFB") (class "Default")
      (node (ref "C28") (pin "1") (pinfunction "1_1") (pintype "input"))
      (node (ref "C29") (pin "1") (pinfunction "1_1") (pintype "input"))
      (node (ref "C30") (pin "1") (pinfunction "1_1") (pintype "input"))
      (node (ref "C31") (pin "1") (pinfunction "1_1") (pintype "input"))
      (node (ref "C36") (pin "1") (pinfunction "1_1") (pintype "input"))
      (node (ref "C37") (pin "1") (pinfunction "1_1") (pintype "input"))
      (node (ref "C38") (pin "1") (pinfunction "1_1") (pintype "input"))
      (node (ref "C39") (pin "1") (pinfunction "1_1") (pintype "input"))
      (node (ref "L2") (pin "2") (pinfunction "2_2") (pintype "input"))
      (node (ref "L3") (pin "2") (pinfunction "2_2") (pintype "input"))
      (node (ref "L4") (pin "2") (pinfunction "2_2") (pintype "input"))
      (node (ref "L5") (pin "2") (pinfunction "2_2") (pintype "input"))
      (node (ref "R49") (pin "2") (pinfunction "2_2") (pintype "input"))
      (node (ref "R52") (pin "2") (pinfunction "2_2") (pintype "input"))
      (node (ref "R53") (pin "2") (pinfunction "2_2") (pintype "input"))
      (node (ref "R54") (pin "2") (pinfunction "2_2") (pintype "input"))
      (node (ref "R55") (pin "2") (pinfunction "2_2") (pintype "input"))
      (node (ref "R57") (pin "2") (pinfunction "2_2") (pintype "input"))
      (node (ref "R58") (pin "1") (pinfunction "1_1") (pintype "input"))
      (node (ref "R64") (pin "2") (pinfunction "2_2") (pintype "input"))
      (node (ref "R65") (pin "2") (pinfunction "2_2") (pintype "input"))
      (node (ref "R66") (pin "2") (pinfunction "2_2") (pintype "input"))
      (node (ref "R67") (pin "2") (pinfunction "2_2") (pintype "input"))
      (node (ref "R69") (pin "2") (pinfunction "2_2") (pintype "input"))
      (node (ref "R70") (pin "1") (pinfunction "1_1") (pintype "input"))
      (node (ref "U10") (pin "8") (pinfunction "VCC_8") (pintype "unspecified"))
      (node (ref "U12") (pin "1") (pinfunction "VCC_1") (pintype "unspecified"))
      (node (ref "U13") (pin "8") (pinfunction "VCC_8") (pintype "unspecified"))
      (node (ref "U9") (pin "1") (pinfunction "VCC_1") (pintype "unspecified"))
    )
    (net (code "108") (name "VCC_3P3") (class "Default")
      (node (ref "C24") (pin "2") (pinfunction "2_2") (pintype "input"))
      (node (ref "C25") (pin "2") (pinfunction "2_2") (pintype "input"))
      (node (ref "C26") (pin "2") (pinfunction "2_2") (pintype "input"))
      (node (ref "C27") (pin "2") (pinfunction "2_2") (pintype "input"))
      (node (ref "L1") (pin "2") (pinfunction "2_2") (pintype "input"))
      (node (ref "R26") (pin "1") (pinfunction "1_1") (pintype "input"))
      (node (ref "R47") (pin "1") (pinfunction "1_1") (pintype "input"))
      (node (ref "R49") (pin "1") (pinfunction "1_1") (pintype "input"))
      (node (ref "U7") (pin "5") (pinfunction "OUT_5") (pintype "unspecified"))
    )
    (net (code "109") (name "VCC_5V") (class "Default")
      (node (ref "C18") (pin "1") (pinfunction "1_1") (pintype "input"))
      (node (ref "C20") (pin "1") (pinfunction "1_1") (pintype "input"))
      (node (ref "C21") (pin "1") (pinfunction "1_1") (pintype "input"))
      (node (ref "C22") (pin "1") (pinfunction "1_1") (pintype "input"))
      (node (ref "C23") (pin "2") (pinfunction "2_2") (pintype "input"))
      (node (ref "F2") (pin "1") (pinfunction "1_1") (pintype "input"))
      (node (ref "R20") (pin "2") (pinfunction "2_2") (pintype "input"))
      (node (ref "U7") (pin "2") (pinfunction "VIN_2") (pintype "unspecified"))
      (node (ref "U7") (pin "8") (pinfunction "EN_8") (pintype "unspecified"))
    )
    (net (code "110") (name "VCC_12V") (class "Default")
      (node (ref "C15") (pin "1") (pinfunction "1_1") (pintype "input"))
      (node (ref "C16") (pin "1") (pinfunction "1_1") (pintype "input"))
      (node (ref "C17") (pin "1") (pinfunction "1_1") (pintype "input"))
      (node (ref "C19") (pin "1") (pinfunction "1_1") (pintype "input"))
      (node (ref "F1") (pin "1") (pinfunction "1_1") (pintype "input"))
      (node (ref "R9") (pin "2") (pinfunction "2_2") (pintype "input"))
    )
    (net (code "111") (name "unconnected-(CON1-PadA5)") (class "Default")
      (node (ref "CON1") (pin "A5") (pinfunction "A5_A5") (pintype "input+no_connect"))
    )
    (net (code "112") (name "unconnected-(CON1-PadA6)") (class "Default")
      (node (ref "CON1") (pin "A6") (pinfunction "A6_A6") (pintype "input+no_connect"))
    )
    (net (code "113") (name "unconnected-(CON1-PadA7)") (class "Default")
      (node (ref "CON1") (pin "A7") (pinfunction "A7_A7") (pintype "input+no_connect"))
    )
    (net (code "114") (name "unconnected-(CON1-PadA15)") (class "Default")
      (node (ref "CON1") (pin "A15") (pinfunction "A15_A15") (pintype "input+no_connect"))
    )
    (net (code "115") (name "unconnected-(CON1-PadA16)") (class "Default")
      (node (ref "CON1") (pin "A16") (pinfunction "A16_A16") (pintype "input+no_connect"))
    )
    (net (code "116") (name "unconnected-(CON1-PadA17)") (class "Default")
      (node (ref "CON1") (pin "A17") (pinfunction "A17_A17") (pintype "input+no_connect"))
    )
    (net (code "117") (name "unconnected-(CON1-PadA18)") (class "Default")
      (node (ref "CON1") (pin "A18") (pinfunction "A18_A18") (pintype "input+no_connect"))
    )
    (net (code "118") (name "unconnected-(CON1-PadA19)") (class "Default")
      (node (ref "CON1") (pin "A19") (pinfunction "A19_A19") (pintype "input+no_connect"))
    )
    (net (code "119") (name "unconnected-(CON1-PadA20)") (class "Default")
      (node (ref "CON1") (pin "A20") (pinfunction "A20_A20") (pintype "input+no_connect"))
    )
    (net (code "120") (name "unconnected-(CON1-PadA21)") (class "Default")
      (node (ref "CON1") (pin "A21") (pinfunction "A21_A21") (pintype "input+no_connect"))
    )
    (net (code "121") (name "unconnected-(CON1-PadA22)") (class "Default")
      (node (ref "CON1") (pin "A22") (pinfunction "A22_A22") (pintype "input+no_connect"))
    )
    (net (code "122") (name "unconnected-(CON1-PadA23)") (class "Default")
      (node (ref "CON1") (pin "A23") (pinfunction "A23_A23") (pintype "input+no_connect"))
    )
    (net (code "123") (name "unconnected-(CON1-PadA24)") (class "Default")
      (node (ref "CON1") (pin "A24") (pinfunction "A24_A24") (pintype "input+no_connect"))
    )
    (net (code "124") (name "unconnected-(CON1-PadA25)") (class "Default")
      (node (ref "CON1") (pin "A25") (pinfunction "A25_A25") (pintype "input+no_connect"))
    )
    (net (code "125") (name "unconnected-(CON1-PadB5)") (class "Default")
      (node (ref "CON1") (pin "B5") (pinfunction "B5_B5") (pintype "input+no_connect"))
    )
    (net (code "126") (name "unconnected-(CON1-PadB6)") (class "Default")
      (node (ref "CON1") (pin "B6") (pinfunction "B6_B6") (pintype "input+no_connect"))
    )
    (net (code "127") (name "unconnected-(CON1-PadB7)") (class "Default")
      (node (ref "CON1") (pin "B7") (pinfunction "B7_B7") (pintype "input+no_connect"))
    )
    (net (code "128") (name "unconnected-(CON1-PadB15)") (class "Default")
      (node (ref "CON1") (pin "B15") (pinfunction "B15_B15") (pintype "input+no_connect"))
    )
    (net (code "129") (name "unconnected-(CON1-PadB16)") (class "Default")
      (node (ref "CON1") (pin "B16") (pinfunction "B16_B16") (pintype "input+no_connect"))
    )
    (net (code "130") (name "unconnected-(CON1-PadB17)") (class "Default")
      (node (ref "CON1") (pin "B17") (pinfunction "B17_B17") (pintype "input+no_connect"))
    )
    (net (code "131") (name "unconnected-(CON1-PadB18)") (class "Default")
      (node (ref "CON1") (pin "B18") (pinfunction "B18_B18") (pintype "input+no_connect"))
    )
    (net (code "132") (name "unconnected-(CON1-PadB19)") (class "Default")
      (node (ref "CON1") (pin "B19") (pinfunction "B19_B19") (pintype "input+no_connect"))
    )
    (net (code "133") (name "unconnected-(CON1-PadB20)") (class "Default")
      (node (ref "CON1") (pin "B20") (pinfunction "B20_B20") (pintype "input+no_connect"))
    )
    (net (code "134") (name "unconnected-(CON1-PadB21)") (class "Default")
      (node (ref "CON1") (pin "B21") (pinfunction "B21_B21") (pintype "input+no_connect"))
    )
    (net (code "135") (name "unconnected-(CON1-PadB22)") (class "Default")
      (node (ref "CON1") (pin "B22") (pinfunction "B22_B22") (pintype "input+no_connect"))
    )
    (net (code "136") (name "unconnected-(CON1-PadB23)") (class "Default")
      (node (ref "CON1") (pin "B23") (pinfunction "B23_B23") (pintype "input+no_connect"))
    )
    (net (code "137") (name "unconnected-(CON1-PadB24)") (class "Default")
      (node (ref "CON1") (pin "B24") (pinfunction "B24_B24") (pintype "input+no_connect"))
    )
    (net (code "138") (name "unconnected-(CON1-PadB25)") (class "Default")
      (node (ref "CON1") (pin "B25") (pinfunction "B25_B25") (pintype "input+no_connect"))
    )
    (net (code "139") (name "unconnected-(CON1-PadC5)") (class "Default")
      (node (ref "CON1") (pin "C5") (pinfunction "C5_C5") (pintype "input+no_connect"))
    )
    (net (code "140") (name "unconnected-(CON1-PadC6)") (class "Default")
      (node (ref "CON1") (pin "C6") (pinfunction "C6_C6") (pintype "input+no_connect"))
    )
    (net (code "141") (name "unconnected-(CON1-PadC7)") (class "Default")
      (node (ref "CON1") (pin "C7") (pinfunction "C7_C7") (pintype "input+no_connect"))
    )
    (net (code "142") (name "unconnected-(CON1-PadC23)") (class "Default")
      (node (ref "CON1") (pin "C23") (pinfunction "C23_C23") (pintype "input+no_connect"))
    )
    (net (code "143") (name "unconnected-(CON1-PadC24)") (class "Default")
      (node (ref "CON1") (pin "C24") (pinfunction "C24_C24") (pintype "input+no_connect"))
    )
    (net (code "144") (name "unconnected-(CON1-PadC25)") (class "Default")
      (node (ref "CON1") (pin "C25") (pinfunction "C25_C25") (pintype "input+no_connect"))
    )
    (net (code "145") (name "unconnected-(CON1-PadD5)") (class "Default")
      (node (ref "CON1") (pin "D5") (pinfunction "D5_D5") (pintype "input+no_connect"))
    )
    (net (code "146") (name "unconnected-(CON1-PadD6)") (class "Default")
      (node (ref "CON1") (pin "D6") (pinfunction "D6_D6") (pintype "input+no_connect"))
    )
    (net (code "147") (name "unconnected-(CON1-PadD7)") (class "Default")
      (node (ref "CON1") (pin "D7") (pinfunction "D7_D7") (pintype "input+no_connect"))
    )
    (net (code "148") (name "unconnected-(CON1-PadD23)") (class "Default")
      (node (ref "CON1") (pin "D23") (pinfunction "D23_D23") (pintype "input+no_connect"))
    )
    (net (code "149") (name "unconnected-(CON1-PadD24)") (class "Default")
      (node (ref "CON1") (pin "D24") (pinfunction "D24_D24") (pintype "input+no_connect"))
    )
    (net (code "150") (name "unconnected-(CON1-PadD25)") (class "Default")
      (node (ref "CON1") (pin "D25") (pinfunction "D25_D25") (pintype "input+no_connect"))
    )
    (net (code "151") (name "unconnected-(CON1-PadE5)") (class "Default")
      (node (ref "CON1") (pin "E5") (pinfunction "E5_E5") (pintype "input+no_connect"))
    )
    (net (code "152") (name "unconnected-(CON1-PadE6)") (class "Default")
      (node (ref "CON1") (pin "E6") (pinfunction "E6_E6") (pintype "input+no_connect"))
    )
    (net (code "153") (name "unconnected-(CON1-PadE7)") (class "Default")
      (node (ref "CON1") (pin "E7") (pinfunction "E7_E7") (pintype "input+no_connect"))
    )
    (net (code "154") (name "unconnected-(CON1-PadE15)") (class "Default")
      (node (ref "CON1") (pin "E15") (pinfunction "E15_E15") (pintype "input+no_connect"))
    )
    (net (code "155") (name "unconnected-(CON1-PadE16)") (class "Default")
      (node (ref "CON1") (pin "E16") (pinfunction "E16_E16") (pintype "input+no_connect"))
    )
    (net (code "156") (name "unconnected-(CON1-PadE17)") (class "Default")
      (node (ref "CON1") (pin "E17") (pinfunction "E17_E17") (pintype "input+no_connect"))
    )
    (net (code "157") (name "unconnected-(CON1-PadE18)") (class "Default")
      (node (ref "CON1") (pin "E18") (pinfunction "E18_E18") (pintype "input+no_connect"))
    )
    (net (code "158") (name "unconnected-(CON1-PadE19)") (class "Default")
      (node (ref "CON1") (pin "E19") (pinfunction "E19_E19") (pintype "input+no_connect"))
    )
    (net (code "159") (name "unconnected-(CON1-PadE20)") (class "Default")
      (node (ref "CON1") (pin "E20") (pinfunction "E20_E20") (pintype "input+no_connect"))
    )
    (net (code "160") (name "unconnected-(CON1-PadE21)") (class "Default")
      (node (ref "CON1") (pin "E21") (pinfunction "E21_E21") (pintype "input+no_connect"))
    )
    (net (code "161") (name "unconnected-(CON1-PadE22)") (class "Default")
      (node (ref "CON1") (pin "E22") (pinfunction "E22_E22") (pintype "input+no_connect"))
    )
    (net (code "162") (name "unconnected-(CON1-PadE23)") (class "Default")
      (node (ref "CON1") (pin "E23") (pinfunction "E23_E23") (pintype "input+no_connect"))
    )
    (net (code "163") (name "unconnected-(CON1-PadE24)") (class "Default")
      (node (ref "CON1") (pin "E24") (pinfunction "E24_E24") (pintype "input+no_connect"))
    )
    (net (code "164") (name "unconnected-(CON1-PadE25)") (class "Default")
      (node (ref "CON1") (pin "E25") (pinfunction "E25_E25") (pintype "input+no_connect"))
    )
    (net (code "165") (name "unconnected-(CON2-PadA1)") (class "Default")
      (node (ref "CON2") (pin "A1") (pinfunction "A1_A1") (pintype "input+no_connect"))
    )
    (net (code "166") (name "unconnected-(CON2-PadA2)") (class "Default")
      (node (ref "CON2") (pin "A2") (pinfunction "A2_A2") (pintype "input+no_connect"))
    )
    (net (code "167") (name "unconnected-(CON2-PadA3)") (class "Default")
      (node (ref "CON2") (pin "A3") (pinfunction "A3_A3") (pintype "input+no_connect"))
    )
    (net (code "168") (name "unconnected-(CON2-PadA4)") (class "Default")
      (node (ref "CON2") (pin "A4") (pinfunction "A4_A4") (pintype "input+no_connect"))
    )
    (net (code "169") (name "unconnected-(CON2-PadA5)") (class "Default")
      (node (ref "CON2") (pin "A5") (pinfunction "A5_A5") (pintype "input+no_connect"))
    )
    (net (code "170") (name "unconnected-(CON2-PadA6)") (class "Default")
      (node (ref "CON2") (pin "A6") (pinfunction "A6_A6") (pintype "input+no_connect"))
    )
    (net (code "171") (name "unconnected-(CON2-PadA7)") (class "Default")
      (node (ref "CON2") (pin "A7") (pinfunction "A7_A7") (pintype "input+no_connect"))
    )
    (net (code "172") (name "unconnected-(CON2-PadA8)") (class "Default")
      (node (ref "CON2") (pin "A8") (pinfunction "A8_A8") (pintype "input+no_connect"))
    )
    (net (code "173") (name "unconnected-(CON2-PadA9)") (class "Default")
      (node (ref "CON2") (pin "A9") (pinfunction "A9_A9") (pintype "input+no_connect"))
    )
    (net (code "174") (name "unconnected-(CON2-PadA10)") (class "Default")
      (node (ref "CON2") (pin "A10") (pinfunction "A10_A10") (pintype "input+no_connect"))
    )
    (net (code "175") (name "unconnected-(CON2-PadA11)") (class "Default")
      (node (ref "CON2") (pin "A11") (pinfunction "A11_A11") (pintype "input+no_connect"))
    )
    (net (code "176") (name "unconnected-(CON2-PadA12)") (class "Default")
      (node (ref "CON2") (pin "A12") (pinfunction "A12_A12") (pintype "input+no_connect"))
    )
    (net (code "177") (name "unconnected-(CON2-PadA13)") (class "Default")
      (node (ref "CON2") (pin "A13") (pinfunction "A13_A13") (pintype "input+no_connect"))
    )
    (net (code "178") (name "unconnected-(CON2-PadA14)") (class "Default")
      (node (ref "CON2") (pin "A14") (pinfunction "A14_A14") (pintype "input+no_connect"))
    )
    (net (code "179") (name "unconnected-(CON2-PadA15)") (class "Default")
      (node (ref "CON2") (pin "A15") (pinfunction "A15_A15") (pintype "input+no_connect"))
    )
    (net (code "180") (name "unconnected-(CON2-PadA16)") (class "Default")
      (node (ref "CON2") (pin "A16") (pinfunction "A16_A16") (pintype "input+no_connect"))
    )
    (net (code "181") (name "unconnected-(CON2-PadA17)") (class "Default")
      (node (ref "CON2") (pin "A17") (pinfunction "A17_A17") (pintype "input+no_connect"))
    )
    (net (code "182") (name "unconnected-(CON2-PadA18)") (class "Default")
      (node (ref "CON2") (pin "A18") (pinfunction "A18_A18") (pintype "input+no_connect"))
    )
    (net (code "183") (name "unconnected-(CON2-PadA19)") (class "Default")
      (node (ref "CON2") (pin "A19") (pinfunction "A19_A19") (pintype "input+no_connect"))
    )
    (net (code "184") (name "unconnected-(CON2-PadA20)") (class "Default")
      (node (ref "CON2") (pin "A20") (pinfunction "A20_A20") (pintype "input+no_connect"))
    )
    (net (code "185") (name "unconnected-(CON2-PadA21)") (class "Default")
      (node (ref "CON2") (pin "A21") (pinfunction "A21_A21") (pintype "input+no_connect"))
    )
    (net (code "186") (name "unconnected-(CON2-PadA22)") (class "Default")
      (node (ref "CON2") (pin "A22") (pinfunction "A22_A22") (pintype "input+no_connect"))
    )
    (net (code "187") (name "unconnected-(CON2-PadB1)") (class "Default")
      (node (ref "CON2") (pin "B1") (pinfunction "B1_B1") (pintype "input+no_connect"))
    )
    (net (code "188") (name "unconnected-(CON2-PadB2)") (class "Default")
      (node (ref "CON2") (pin "B2") (pinfunction "B2_B2") (pintype "input+no_connect"))
    )
    (net (code "189") (name "unconnected-(CON2-PadB3)") (class "Default")
      (node (ref "CON2") (pin "B3") (pinfunction "B3_B3") (pintype "input+no_connect"))
    )
    (net (code "190") (name "unconnected-(CON2-PadB4)") (class "Default")
      (node (ref "CON2") (pin "B4") (pinfunction "B4_B4") (pintype "input+no_connect"))
    )
    (net (code "191") (name "unconnected-(CON2-PadB5)") (class "Default")
      (node (ref "CON2") (pin "B5") (pinfunction "B5_B5") (pintype "input+no_connect"))
    )
    (net (code "192") (name "unconnected-(CON2-PadB6)") (class "Default")
      (node (ref "CON2") (pin "B6") (pinfunction "B6_B6") (pintype "input+no_connect"))
    )
    (net (code "193") (name "unconnected-(CON2-PadB7)") (class "Default")
      (node (ref "CON2") (pin "B7") (pinfunction "B7_B7") (pintype "input+no_connect"))
    )
    (net (code "194") (name "unconnected-(CON2-PadB8)") (class "Default")
      (node (ref "CON2") (pin "B8") (pinfunction "B8_B8") (pintype "input+no_connect"))
    )
    (net (code "195") (name "unconnected-(CON2-PadB9)") (class "Default")
      (node (ref "CON2") (pin "B9") (pinfunction "B9_B9") (pintype "input+no_connect"))
    )
    (net (code "196") (name "unconnected-(CON2-PadB10)") (class "Default")
      (node (ref "CON2") (pin "B10") (pinfunction "B10_B10") (pintype "input+no_connect"))
    )
    (net (code "197") (name "unconnected-(CON2-PadB11)") (class "Default")
      (node (ref "CON2") (pin "B11") (pinfunction "B11_B11") (pintype "input+no_connect"))
    )
    (net (code "198") (name "unconnected-(CON2-PadB12)") (class "Default")
      (node (ref "CON2") (pin "B12") (pinfunction "B12_B12") (pintype "input+no_connect"))
    )
    (net (code "199") (name "unconnected-(CON2-PadB13)") (class "Default")
      (node (ref "CON2") (pin "B13") (pinfunction "B13_B13") (pintype "input+no_connect"))
    )
    (net (code "200") (name "unconnected-(CON2-PadB14)") (class "Default")
      (node (ref "CON2") (pin "B14") (pinfunction "B14_B14") (pintype "input+no_connect"))
    )
    (net (code "201") (name "unconnected-(CON2-PadB15)") (class "Default")
      (node (ref "CON2") (pin "B15") (pinfunction "B15_B15") (pintype "input+no_connect"))
    )
    (net (code "202") (name "unconnected-(CON2-PadB16)") (class "Default")
      (node (ref "CON2") (pin "B16") (pinfunction "B16_B16") (pintype "input+no_connect"))
    )
    (net (code "203") (name "unconnected-(CON2-PadB17)") (class "Default")
      (node (ref "CON2") (pin "B17") (pinfunction "B17_B17") (pintype "input+no_connect"))
    )
    (net (code "204") (name "unconnected-(CON2-PadB18)") (class "Default")
      (node (ref "CON2") (pin "B18") (pinfunction "B18_B18") (pintype "input+no_connect"))
    )
    (net (code "205") (name "unconnected-(CON2-PadB19)") (class "Default")
      (node (ref "CON2") (pin "B19") (pinfunction "B19_B19") (pintype "input+no_connect"))
    )
    (net (code "206") (name "unconnected-(CON2-PadB20)") (class "Default")
      (node (ref "CON2") (pin "B20") (pinfunction "B20_B20") (pintype "input+no_connect"))
    )
    (net (code "207") (name "unconnected-(CON2-PadB21)") (class "Default")
      (node (ref "CON2") (pin "B21") (pinfunction "B21_B21") (pintype "input+no_connect"))
    )
    (net (code "208") (name "unconnected-(CON2-PadB22)") (class "Default")
      (node (ref "CON2") (pin "B22") (pinfunction "B22_B22") (pintype "input+no_connect"))
    )
    (net (code "209") (name "unconnected-(CON2-PadC1)") (class "Default")
      (node (ref "CON2") (pin "C1") (pinfunction "C1_C1") (pintype "input+no_connect"))
    )
    (net (code "210") (name "unconnected-(CON2-PadC2)") (class "Default")
      (node (ref "CON2") (pin "C2") (pinfunction "C2_C2") (pintype "input+no_connect"))
    )
    (net (code "211") (name "unconnected-(CON2-PadC3)") (class "Default")
      (node (ref "CON2") (pin "C3") (pinfunction "C3_C3") (pintype "input+no_connect"))
    )
    (net (code "212") (name "unconnected-(CON2-PadC4)") (class "Default")
      (node (ref "CON2") (pin "C4") (pinfunction "C4_C4") (pintype "input+no_connect"))
    )
    (net (code "213") (name "unconnected-(CON2-PadC5)") (class "Default")
      (node (ref "CON2") (pin "C5") (pinfunction "C5_C5") (pintype "input+no_connect"))
    )
    (net (code "214") (name "unconnected-(CON2-PadC6)") (class "Default")
      (node (ref "CON2") (pin "C6") (pinfunction "C6_C6") (pintype "input+no_connect"))
    )
    (net (code "215") (name "unconnected-(CON2-PadC7)") (class "Default")
      (node (ref "CON2") (pin "C7") (pinfunction "C7_C7") (pintype "input+no_connect"))
    )
    (net (code "216") (name "unconnected-(CON2-PadC8)") (class "Default")
      (node (ref "CON2") (pin "C8") (pinfunction "C8_C8") (pintype "input+no_connect"))
    )
    (net (code "217") (name "unconnected-(CON2-PadC9)") (class "Default")
      (node (ref "CON2") (pin "C9") (pinfunction "C9_C9") (pintype "input+no_connect"))
    )
    (net (code "218") (name "unconnected-(CON2-PadC10)") (class "Default")
      (node (ref "CON2") (pin "C10") (pinfunction "C10_C10") (pintype "input+no_connect"))
    )
    (net (code "219") (name "unconnected-(CON2-PadC11)") (class "Default")
      (node (ref "CON2") (pin "C11") (pinfunction "C11_C11") (pintype "input+no_connect"))
    )
    (net (code "220") (name "unconnected-(CON2-PadC12)") (class "Default")
      (node (ref "CON2") (pin "C12") (pinfunction "C12_C12") (pintype "input+no_connect"))
    )
    (net (code "221") (name "unconnected-(CON2-PadC13)") (class "Default")
      (node (ref "CON2") (pin "C13") (pinfunction "C13_C13") (pintype "input+no_connect"))
    )
    (net (code "222") (name "unconnected-(CON2-PadC14)") (class "Default")
      (node (ref "CON2") (pin "C14") (pinfunction "C14_C14") (pintype "input+no_connect"))
    )
    (net (code "223") (name "unconnected-(CON2-PadC15)") (class "Default")
      (node (ref "CON2") (pin "C15") (pinfunction "C15_C15") (pintype "input+no_connect"))
    )
    (net (code "224") (name "unconnected-(CON2-PadC16)") (class "Default")
      (node (ref "CON2") (pin "C16") (pinfunction "C16_C16") (pintype "input+no_connect"))
    )
    (net (code "225") (name "unconnected-(CON2-PadC17)") (class "Default")
      (node (ref "CON2") (pin "C17") (pinfunction "C17_C17") (pintype "input+no_connect"))
    )
    (net (code "226") (name "unconnected-(CON2-PadC18)") (class "Default")
      (node (ref "CON2") (pin "C18") (pinfunction "C18_C18") (pintype "input+no_connect"))
    )
    (net (code "227") (name "unconnected-(CON2-PadC19)") (class "Default")
      (node (ref "CON2") (pin "C19") (pinfunction "C19_C19") (pintype "input+no_connect"))
    )
    (net (code "228") (name "unconnected-(CON2-PadC20)") (class "Default")
      (node (ref "CON2") (pin "C20") (pinfunction "C20_C20") (pintype "input+no_connect"))
    )
    (net (code "229") (name "unconnected-(CON2-PadC21)") (class "Default")
      (node (ref "CON2") (pin "C21") (pinfunction "C21_C21") (pintype "input+no_connect"))
    )
    (net (code "230") (name "unconnected-(CON2-PadC22)") (class "Default")
      (node (ref "CON2") (pin "C22") (pinfunction "C22_C22") (pintype "input+no_connect"))
    )
    (net (code "231") (name "unconnected-(CON2-PadD1)") (class "Default")
      (node (ref "CON2") (pin "D1") (pinfunction "D1_D1") (pintype "input+no_connect"))
    )
    (net (code "232") (name "unconnected-(CON2-PadD2)") (class "Default")
      (node (ref "CON2") (pin "D2") (pinfunction "D2_D2") (pintype "input+no_connect"))
    )
    (net (code "233") (name "unconnected-(CON2-PadD3)") (class "Default")
      (node (ref "CON2") (pin "D3") (pinfunction "D3_D3") (pintype "input+no_connect"))
    )
    (net (code "234") (name "unconnected-(CON2-PadD4)") (class "Default")
      (node (ref "CON2") (pin "D4") (pinfunction "D4_D4") (pintype "input+no_connect"))
    )
    (net (code "235") (name "unconnected-(CON2-PadD5)") (class "Default")
      (node (ref "CON2") (pin "D5") (pinfunction "D5_D5") (pintype "input+no_connect"))
    )
    (net (code "236") (name "unconnected-(CON2-PadD6)") (class "Default")
      (node (ref "CON2") (pin "D6") (pinfunction "D6_D6") (pintype "input+no_connect"))
    )
    (net (code "237") (name "unconnected-(CON2-PadD7)") (class "Default")
      (node (ref "CON2") (pin "D7") (pinfunction "D7_D7") (pintype "input+no_connect"))
    )
    (net (code "238") (name "unconnected-(CON2-PadD8)") (class "Default")
      (node (ref "CON2") (pin "D8") (pinfunction "D8_D8") (pintype "input+no_connect"))
    )
    (net (code "239") (name "unconnected-(CON2-PadD9)") (class "Default")
      (node (ref "CON2") (pin "D9") (pinfunction "D9_D9") (pintype "input+no_connect"))
    )
    (net (code "240") (name "unconnected-(CON2-PadD10)") (class "Default")
      (node (ref "CON2") (pin "D10") (pinfunction "D10_D10") (pintype "input+no_connect"))
    )
    (net (code "241") (name "unconnected-(CON2-PadD11)") (class "Default")
      (node (ref "CON2") (pin "D11") (pinfunction "D11_D11") (pintype "input+no_connect"))
    )
    (net (code "242") (name "unconnected-(CON2-PadD12)") (class "Default")
      (node (ref "CON2") (pin "D12") (pinfunction "D12_D12") (pintype "input+no_connect"))
    )
    (net (code "243") (name "unconnected-(CON2-PadD13)") (class "Default")
      (node (ref "CON2") (pin "D13") (pinfunction "D13_D13") (pintype "input+no_connect"))
    )
    (net (code "244") (name "unconnected-(CON2-PadD14)") (class "Default")
      (node (ref "CON2") (pin "D14") (pinfunction "D14_D14") (pintype "input+no_connect"))
    )
    (net (code "245") (name "unconnected-(CON2-PadD15)") (class "Default")
      (node (ref "CON2") (pin "D15") (pinfunction "D15_D15") (pintype "input+no_connect"))
    )
    (net (code "246") (name "unconnected-(CON2-PadD16)") (class "Default")
      (node (ref "CON2") (pin "D16") (pinfunction "D16_D16") (pintype "input+no_connect"))
    )
    (net (code "247") (name "unconnected-(CON2-PadD17)") (class "Default")
      (node (ref "CON2") (pin "D17") (pinfunction "D17_D17") (pintype "input+no_connect"))
    )
    (net (code "248") (name "unconnected-(CON2-PadD18)") (class "Default")
      (node (ref "CON2") (pin "D18") (pinfunction "D18_D18") (pintype "input+no_connect"))
    )
    (net (code "249") (name "unconnected-(CON2-PadE1)") (class "Default")
      (node (ref "CON2") (pin "E1") (pinfunction "E1_E1") (pintype "input+no_connect"))
    )
    (net (code "250") (name "unconnected-(CON2-PadE2)") (class "Default")
      (node (ref "CON2") (pin "E2") (pinfunction "E2_E2") (pintype "input+no_connect"))
    )
    (net (code "251") (name "unconnected-(CON2-PadE3)") (class "Default")
      (node (ref "CON2") (pin "E3") (pinfunction "E3_E3") (pintype "input+no_connect"))
    )
    (net (code "252") (name "unconnected-(CON2-PadE4)") (class "Default")
      (node (ref "CON2") (pin "E4") (pinfunction "E4_E4") (pintype "input+no_connect"))
    )
    (net (code "253") (name "unconnected-(CON2-PadE5)") (class "Default")
      (node (ref "CON2") (pin "E5") (pinfunction "E5_E5") (pintype "input+no_connect"))
    )
    (net (code "254") (name "unconnected-(CON2-PadE6)") (class "Default")
      (node (ref "CON2") (pin "E6") (pinfunction "E6_E6") (pintype "input+no_connect"))
    )
    (net (code "255") (name "unconnected-(CON2-PadE7)") (class "Default")
      (node (ref "CON2") (pin "E7") (pinfunction "E7_E7") (pintype "input+no_connect"))
    )
    (net (code "256") (name "unconnected-(CON2-PadE8)") (class "Default")
      (node (ref "CON2") (pin "E8") (pinfunction "E8_E8") (pintype "input+no_connect"))
    )
    (net (code "257") (name "unconnected-(CON2-PadE9)") (class "Default")
      (node (ref "CON2") (pin "E9") (pinfunction "E9_E9") (pintype "input+no_connect"))
    )
    (net (code "258") (name "unconnected-(CON2-PadE10)") (class "Default")
      (node (ref "CON2") (pin "E10") (pinfunction "E10_E10") (pintype "input+no_connect"))
    )
    (net (code "259") (name "unconnected-(CON2-PadE11)") (class "Default")
      (node (ref "CON2") (pin "E11") (pinfunction "E11_E11") (pintype "input+no_connect"))
    )
    (net (code "260") (name "unconnected-(CON2-PadE12)") (class "Default")
      (node (ref "CON2") (pin "E12") (pinfunction "E12_E12") (pintype "input+no_connect"))
    )
    (net (code "261") (name "unconnected-(CON2-PadE13)") (class "Default")
      (node (ref "CON2") (pin "E13") (pinfunction "E13_E13") (pintype "input+no_connect"))
    )
    (net (code "262") (name "unconnected-(CON2-PadE14)") (class "Default")
      (node (ref "CON2") (pin "E14") (pinfunction "E14_E14") (pintype "input+no_connect"))
    )
    (net (code "263") (name "unconnected-(CON2-PadE15)") (class "Default")
      (node (ref "CON2") (pin "E15") (pinfunction "E15_E15") (pintype "input+no_connect"))
    )
    (net (code "264") (name "unconnected-(CON2-PadE16)") (class "Default")
      (node (ref "CON2") (pin "E16") (pinfunction "E16_E16") (pintype "input+no_connect"))
    )
    (net (code "265") (name "unconnected-(CON2-PadE19)") (class "Default")
      (node (ref "CON2") (pin "E19") (pinfunction "E19_E19") (pintype "input+no_connect"))
    )
    (net (code "266") (name "unconnected-(CON2-PadE20)") (class "Default")
      (node (ref "CON2") (pin "E20") (pinfunction "E20_E20") (pintype "input+no_connect"))
    )
    (net (code "267") (name "unconnected-(CON2-PadE21)") (class "Default")
      (node (ref "CON2") (pin "E21") (pinfunction "E21_E21") (pintype "input+no_connect"))
    )
    (net (code "268") (name "unconnected-(CON2-PadE22)") (class "Default")
      (node (ref "CON2") (pin "E22") (pinfunction "E22_E22") (pintype "input+no_connect"))
    )
    (net (code "269") (name "unconnected-(U1-Y4-Pad1)") (class "Default")
      (node (ref "U1") (pin "1") (pinfunction "Y4_1") (pintype "unspecified+no_connect"))
    )
    (net (code "270") (name "unconnected-(U1-Y5-Pad5)") (class "Default")
      (node (ref "U1") (pin "5") (pinfunction "Y5_5") (pintype "unspecified+no_connect"))
    )
    (net (code "271") (name "unconnected-(U1-Y6-Pad2)") (class "Default")
      (node (ref "U1") (pin "2") (pinfunction "Y6_2") (pintype "unspecified+no_connect"))
    )
    (net (code "272") (name "unconnected-(U1-Y7-Pad4)") (class "Default")
      (node (ref "U1") (pin "4") (pinfunction "Y7_4") (pintype "unspecified+no_connect"))
    )
    (net (code "273") (name "unconnected-(U2-Y4-Pad1)") (class "Default")
      (node (ref "U2") (pin "1") (pinfunction "Y4_1") (pintype "unspecified+no_connect"))
    )
    (net (code "274") (name "unconnected-(U2-Y5-Pad5)") (class "Default")
      (node (ref "U2") (pin "5") (pinfunction "Y5_5") (pintype "unspecified+no_connect"))
    )
    (net (code "275") (name "unconnected-(U2-Y6-Pad2)") (class "Default")
      (node (ref "U2") (pin "2") (pinfunction "Y6_2") (pintype "unspecified+no_connect"))
    )
    (net (code "276") (name "unconnected-(U2-Y7-Pad4)") (class "Default")
      (node (ref "U2") (pin "4") (pinfunction "Y7_4") (pintype "unspecified+no_connect"))
    )
    (net (code "277") (name "unconnected-(U3-Y4-Pad1)") (class "Default")
      (node (ref "U3") (pin "1") (pinfunction "Y4_1") (pintype "unspecified+no_connect"))
    )
    (net (code "278") (name "unconnected-(U3-Y5-Pad5)") (class "Default")
      (node (ref "U3") (pin "5") (pinfunction "Y5_5") (pintype "unspecified+no_connect"))
    )
    (net (code "279") (name "unconnected-(U3-Y6-Pad2)") (class "Default")
      (node (ref "U3") (pin "2") (pinfunction "Y6_2") (pintype "unspecified+no_connect"))
    )
    (net (code "280") (name "unconnected-(U3-Y7-Pad4)") (class "Default")
      (node (ref "U3") (pin "4") (pinfunction "Y7_4") (pintype "unspecified+no_connect"))
    )
    (net (code "281") (name "unconnected-(U4-Y4-Pad1)") (class "Default")
      (node (ref "U4") (pin "1") (pinfunction "Y4_1") (pintype "unspecified+no_connect"))
    )
    (net (code "282") (name "unconnected-(U4-Y5-Pad5)") (class "Default")
      (node (ref "U4") (pin "5") (pinfunction "Y5_5") (pintype "unspecified+no_connect"))
    )
    (net (code "283") (name "unconnected-(U4-Y6-Pad2)") (class "Default")
      (node (ref "U4") (pin "2") (pinfunction "Y6_2") (pintype "unspecified+no_connect"))
    )
    (net (code "284") (name "unconnected-(U4-Y7-Pad4)") (class "Default")
      (node (ref "U4") (pin "4") (pinfunction "Y7_4") (pintype "unspecified+no_connect"))
    )
    (net (code "285") (name "unconnected-(U5-AN6{slash}OA3OUT{slash}C4IN1+{slash}OCFB{slash}RC0-Pad21)") (class "Default")
      (node (ref "U5") (pin "21") (pinfunction "AN6/OA3OUT/C4IN1+/OCFB/RC0_21") (pintype "input+no_connect"))
    )
    (net (code "286") (name "unconnected-(U5-AN7{slash}C3IN1-{slash}C4IN1-{slash}RC1-Pad22)") (class "Default")
      (node (ref "U5") (pin "22") (pinfunction "AN7/C3IN1-/C4IN1-/RC1_22") (pintype "input+no_connect"))
    )
    (net (code "287") (name "unconnected-(U5-AN8{slash}C3IN1+{slash}#U1RTS{slash}BCLK1{slash}RC2-Pad23)") (class "Default")
      (node (ref "U5") (pin "23") (pinfunction "AN8/C3IN1+/#U1RTS/BCLK1/RC2_23") (pintype "input+no_connect"))
    )
    (net (code "288") (name "unconnected-(U5-AN9{slash}RPI27{slash}RA11-Pad12)") (class "Default")
      (node (ref "U5") (pin "12") (pinfunction "AN9/RPI27/RA11_12") (pintype "input+no_connect"))
    )
    (net (code "289") (name "unconnected-(U5-AN11{slash}C11N2-{slash}#U1CTS{slash}RC11-Pad24)") (class "Default")
      (node (ref "U5") (pin "24") (pinfunction "AN11/C11N2-/#U1CTS/RC11_24") (pintype "input+no_connect"))
    )
    (net (code "290") (name "unconnected-(U5-AN12{slash}C2IN2-{slash}#U2RTS{slash}BCLK2{slash}RE12-Pad27)") (class "Default")
      (node (ref "U5") (pin "27") (pinfunction "AN12/C2IN2-/#U2RTS/BCLK2/RE12_27") (pintype "input+no_connect"))
    )
    (net (code "291") (name "unconnected-(U5-AN13{slash}C3IN2-{slash}#U2CTS{slash}RE13-Pad28)") (class "Default")
      (node (ref "U5") (pin "28") (pinfunction "AN13/C3IN2-/#U2CTS/RE13_28") (pintype "input+no_connect"))
    )
    (net (code "292") (name "unconnected-(U5-PGEC2{slash}ASCL2{slash}RP38{slash}RB6-Pad44)") (class "Default")
      (node (ref "U5") (pin "44") (pinfunction "PGEC2/ASCL2/RP38/RB6_44") (pintype "input+no_connect"))
    )
    (net (code "293") (name "unconnected-(U5-PGEC3{slash}VREF+{slash}AN3{slash}OA1OUT{slash}RPI33{slash}CTED1{slash}RB1-Pad16)") (class "Default")
      (node (ref "U5") (pin "16") (pinfunction "PGEC3/VREF+/AN3/OA1OUT/RPI33/CTED1/RB1_16") (pintype "input+no_connect"))
    )
    (net (code "294") (name "unconnected-(U5-PGED3{slash}VREF-{slash}AN2{slash}C2IN1-{slash}#SS1{slash}RPI32{slash}CTED2{slash}RB0-Pad15)") (class "Default")
      (node (ref "U5") (pin "15") (pinfunction "PGED3/VREF-/AN2/C2IN1-/#SS1/RPI32/CTED2/RB0_15") (pintype "input+no_connect"))
    )
    (net (code "295") (name "unconnected-(U5-RC13-Pad47)") (class "Default")
      (node (ref "U5") (pin "47") (pinfunction "RC13_47") (pintype "input+no_connect"))
    )
    (net (code "296") (name "unconnected-(U5-RD5-Pad53)") (class "Default")
      (node (ref "U5") (pin "53") (pinfunction "RD5_53") (pintype "input+no_connect"))
    )
    (net (code "297") (name "unconnected-(U5-RD6-Pad54)") (class "Default")
      (node (ref "U5") (pin "54") (pinfunction "RD6_54") (pintype "input+no_connect"))
    )
    (net (code "298") (name "unconnected-(U5-RP39{slash}INT0{slash}RB7-Pad46)") (class "Default")
      (node (ref "U5") (pin "46") (pinfunction "RP39/INT0/RB7_46") (pintype "input+no_connect"))
    )
    (net (code "299") (name "unconnected-(U5-RP56{slash}RC8-Pad52)") (class "Default")
      (node (ref "U5") (pin "52") (pinfunction "RP56/RC8_52") (pintype "input+no_connect"))
    )
    (net (code "300") (name "unconnected-(U5-RP57{slash}RC9-Pad55)") (class "Default")
      (node (ref "U5") (pin "55") (pinfunction "RP57/RC9_55") (pintype "input+no_connect"))
    )
    (net (code "301") (name "unconnected-(U5-RPI58{slash}RC10-Pad45)") (class "Default")
      (node (ref "U5") (pin "45") (pinfunction "RPI58/RC10_45") (pintype "input+no_connect"))
    )
    (net (code "302") (name "unconnected-(U5-RPI96{slash}RF0-Pad58)") (class "Default")
      (node (ref "U5") (pin "58") (pinfunction "RPI96/RF0_58") (pintype "input+no_connect"))
    )
    (net (code "303") (name "unconnected-(U5-SCK1{slash}RPI51{slash}RC3-Pad35)") (class "Default")
      (node (ref "U5") (pin "35") (pinfunction "SCK1/RPI51/RC3_35") (pintype "input+no_connect"))
    )
    (net (code "304") (name "unconnected-(U5-SCL1{slash}RPI53{slash}RC5-Pad37)") (class "Default")
      (node (ref "U5") (pin "37") (pinfunction "SCL1/RPI53/RC5_37") (pintype "input+no_connect"))
    )
    (net (code "305") (name "unconnected-(U5-SDA1{slash}RPI52{slash}RC4-Pad36)") (class "Default")
      (node (ref "U5") (pin "36") (pinfunction "SDA1/RPI52/RC4_36") (pintype "input+no_connect"))
    )
    (net (code "306") (name "unconnected-(U5-TCK{slash}CVref10{slash}ASCL1{slash}RP40{slash}T4CK{slash}RB8-Pad48)") (class "Default")
      (node (ref "U5") (pin "48") (pinfunction "TCK/CVref10/ASCL1/RP40/T4CK/RB8_48") (pintype "input+no_connect"))
    )
    (net (code "307") (name "unconnected-(U5-TMS{slash}ASDA1{slash}RP41{slash}RB9-Pad49)") (class "Default")
      (node (ref "U5") (pin "49") (pinfunction "TMS/ASDA1/RP41/RB9_49") (pintype "input+no_connect"))
    )
    (net (code "308") (name "unconnected-(U7-PG-Pad1)") (class "Default")
      (node (ref "U7") (pin "1") (pinfunction "PG_1") (pintype "unspecified+no_connect"))
    )
    (net (code "309") (name "unconnected-(U8-NC-Pad10)") (class "Default")
      (node (ref "U8") (pin "10") (pinfunction "NC_10") (pintype "input+no_connect"))
    )
    (net (code "310") (name "unconnected-(U8-NC-Pad11)") (class "Default")
      (node (ref "U8") (pin "11") (pinfunction "NC_11") (pintype "input+no_connect"))
    )
    (net (code "311") (name "unconnected-(U9-N.C.-Pad3)") (class "Default")
      (node (ref "U9") (pin "3") (pinfunction "N.C._3") (pintype "unspecified+no_connect"))
    )
    (net (code "312") (name "unconnected-(U9-N.C.-Pad5)") (class "Default")
      (node (ref "U9") (pin "5") (pinfunction "N.C._5") (pintype "unspecified+no_connect"))
    )
    (net (code "313") (name "unconnected-(U9-N.C.-Pad6)") (class "Default")
      (node (ref "U9") (pin "6") (pinfunction "N.C._6") (pintype "unspecified+no_connect"))
    )
    (net (code "314") (name "unconnected-(U10-NC-Pad3)") (class "Default")
      (node (ref "U10") (pin "3") (pinfunction "NC_3") (pintype "unspecified+no_connect"))
    )
    (net (code "315") (name "unconnected-(U10-NC-Pad4)") (class "Default")
      (node (ref "U10") (pin "4") (pinfunction "NC_4") (pintype "unspecified+no_connect"))
    )
    (net (code "316") (name "unconnected-(U10-NC-Pad6)") (class "Default")
      (node (ref "U10") (pin "6") (pinfunction "NC_6") (pintype "unspecified+no_connect"))
    )
    (net (code "317") (name "unconnected-(U11-NC-Pad10)") (class "Default")
      (node (ref "U11") (pin "10") (pinfunction "NC_10") (pintype "input+no_connect"))
    )
    (net (code "318") (name "unconnected-(U11-NC-Pad11)") (class "Default")
      (node (ref "U11") (pin "11") (pinfunction "NC_11") (pintype "input+no_connect"))
    )
    (net (code "319") (name "unconnected-(U12-N.C.-Pad3)") (class "Default")
      (node (ref "U12") (pin "3") (pinfunction "N.C._3") (pintype "unspecified+no_connect"))
    )
    (net (code "320") (name "unconnected-(U12-N.C.-Pad5)") (class "Default")
      (node (ref "U12") (pin "5") (pinfunction "N.C._5") (pintype "unspecified+no_connect"))
    )
    (net (code "321") (name "unconnected-(U12-N.C.-Pad6)") (class "Default")
      (node (ref "U12") (pin "6") (pinfunction "N.C._6") (pintype "unspecified+no_connect"))
    )
    (net (code "322") (name "unconnected-(U13-NC-Pad3)") (class "Default")
      (node (ref "U13") (pin "3") (pinfunction "NC_3") (pintype "unspecified+no_connect"))
    )
    (net (code "323") (name "unconnected-(U13-NC-Pad4)") (class "Default")
      (node (ref "U13") (pin "4") (pinfunction "NC_4") (pintype "unspecified+no_connect"))
    )
    (net (code "324") (name "unconnected-(U13-NC-Pad6)") (class "Default")
      (node (ref "U13") (pin "6") (pinfunction "NC_6") (pintype "unspecified+no_connect"))
    )
  )
)
